# Shutdown_2019_v1_1.net
KiCad netlist of a schematic drawn in EAGLE
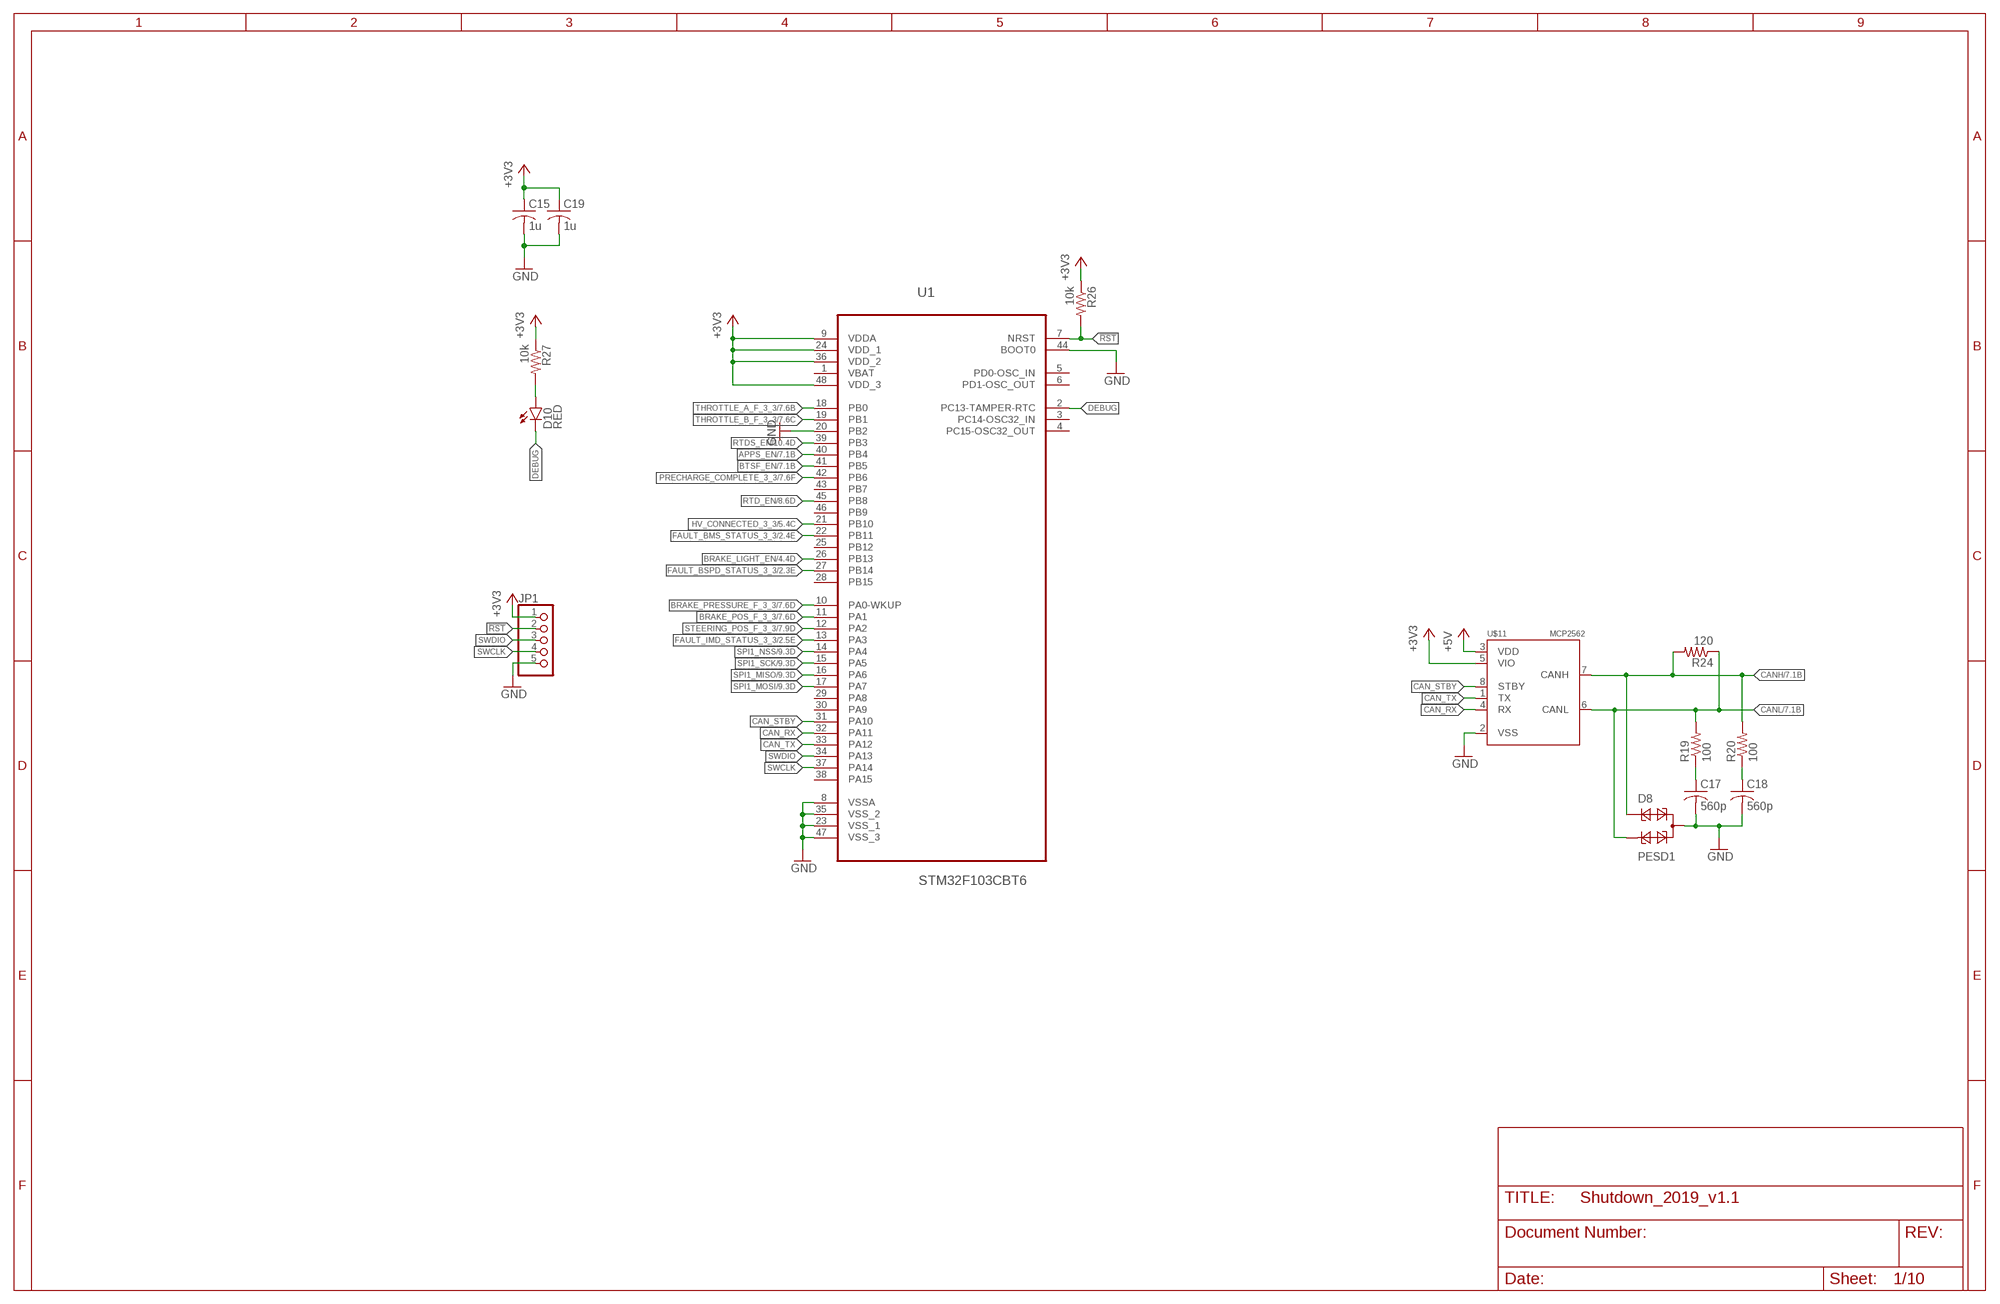
[diagram p0: schematic, sheet 1]
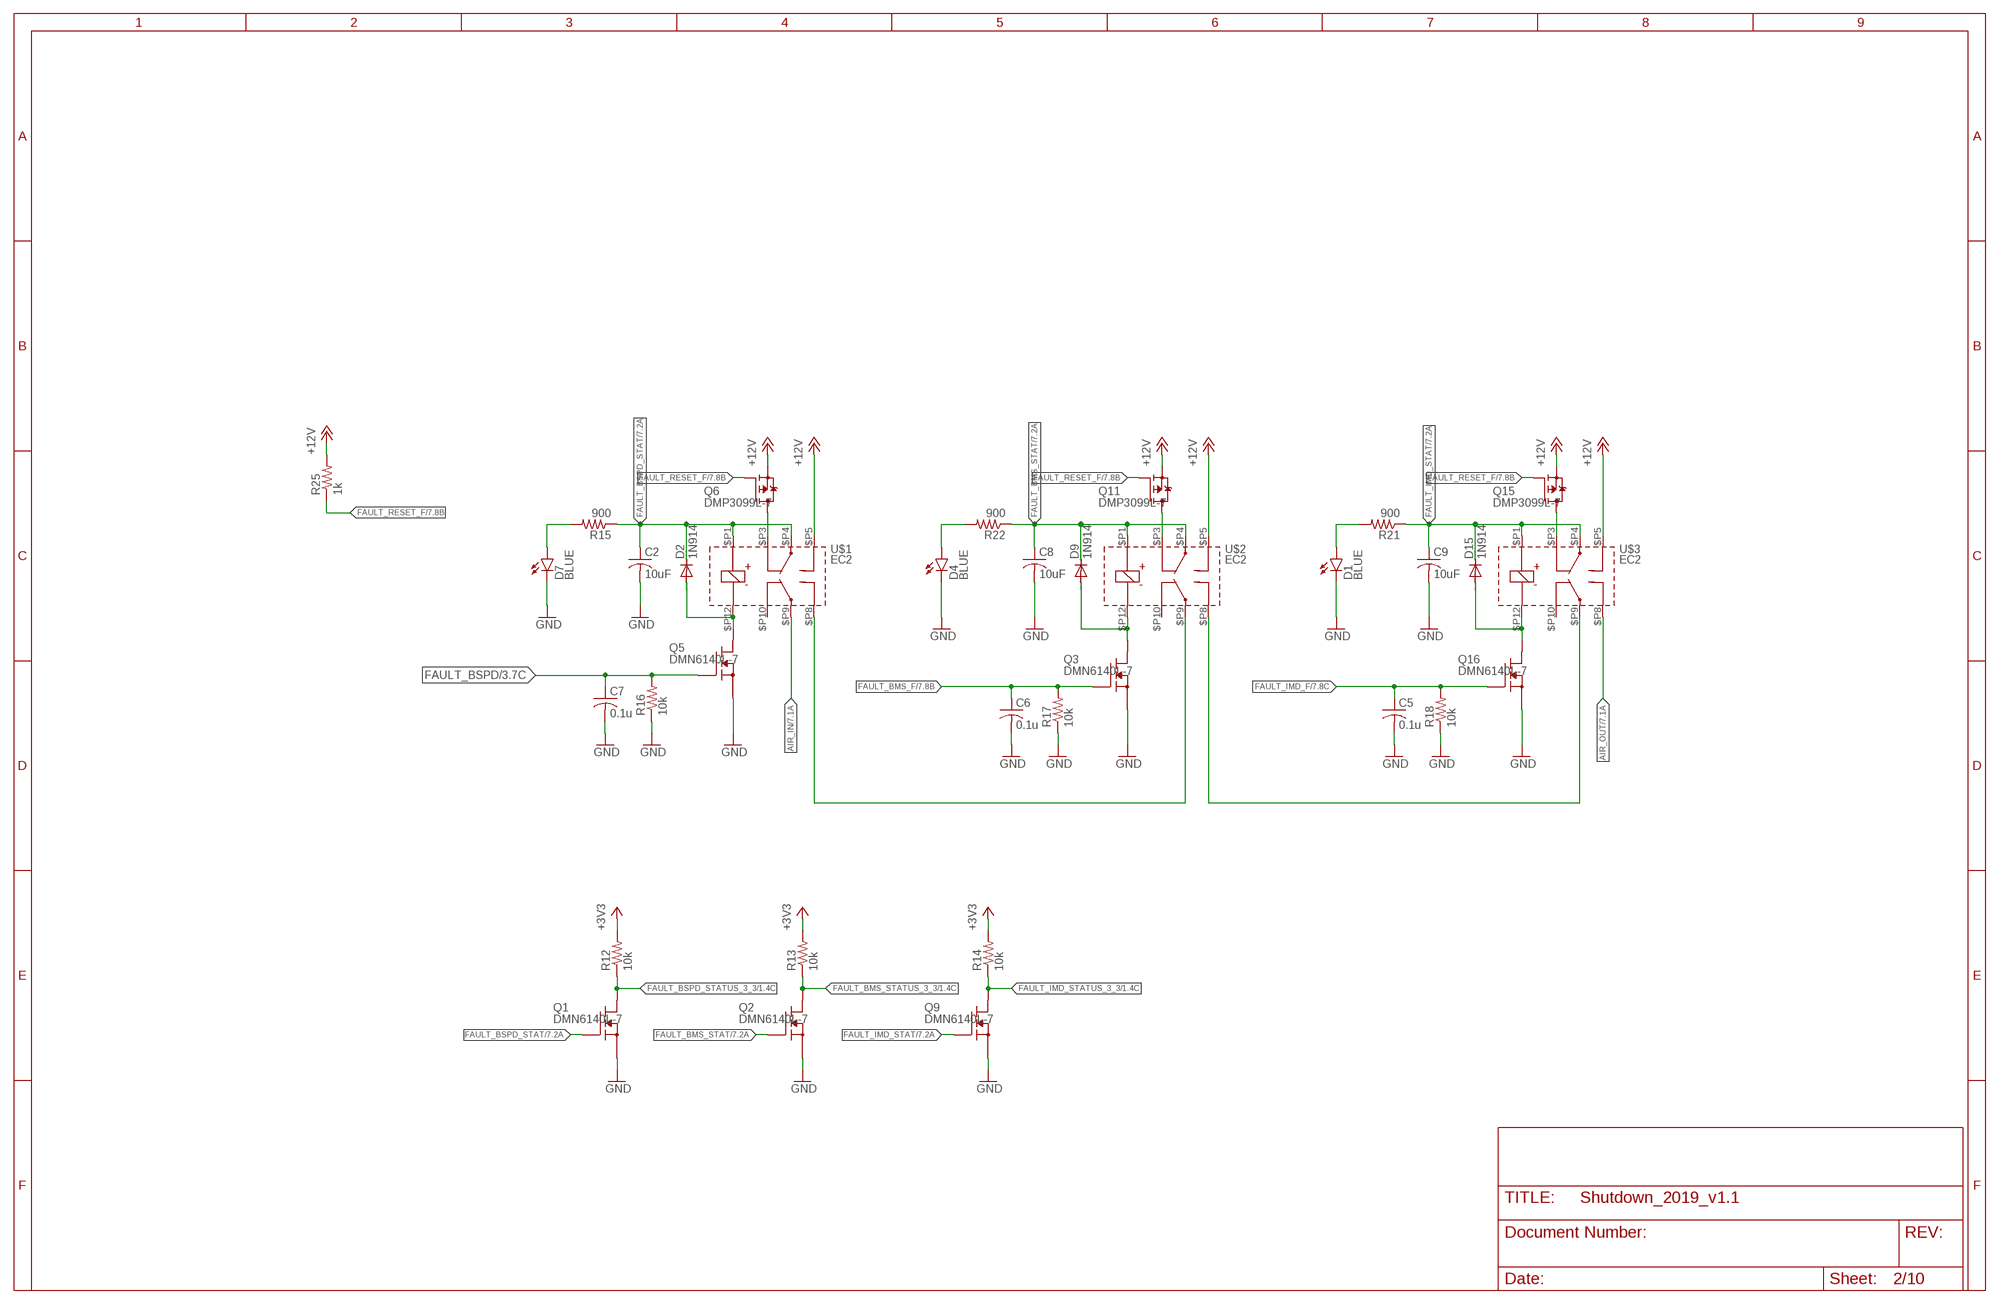
[diagram p1: schematic, sheet 2]
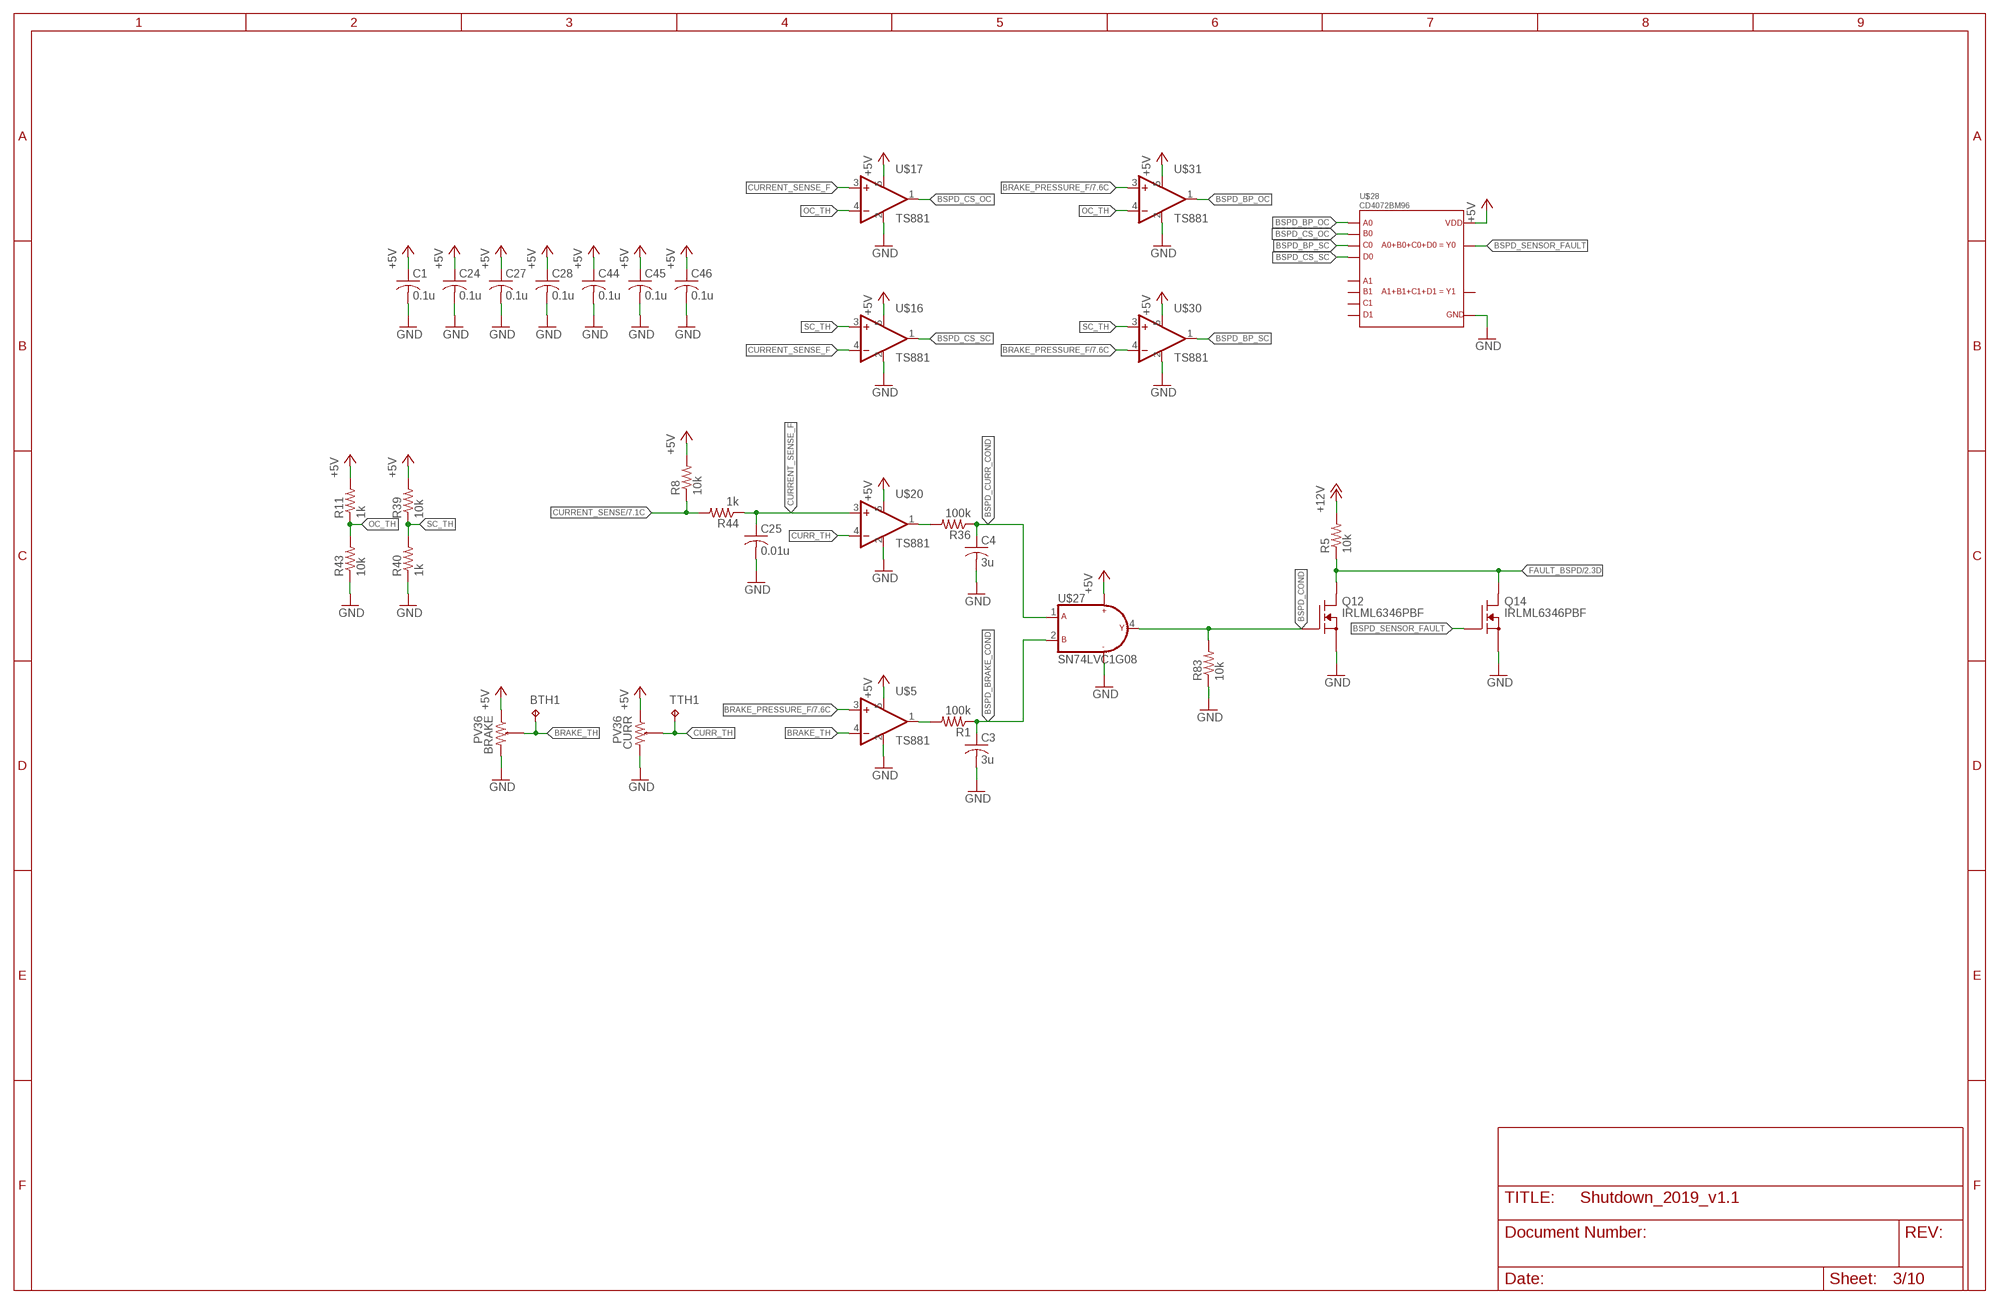
[diagram p2: schematic, sheet 3]
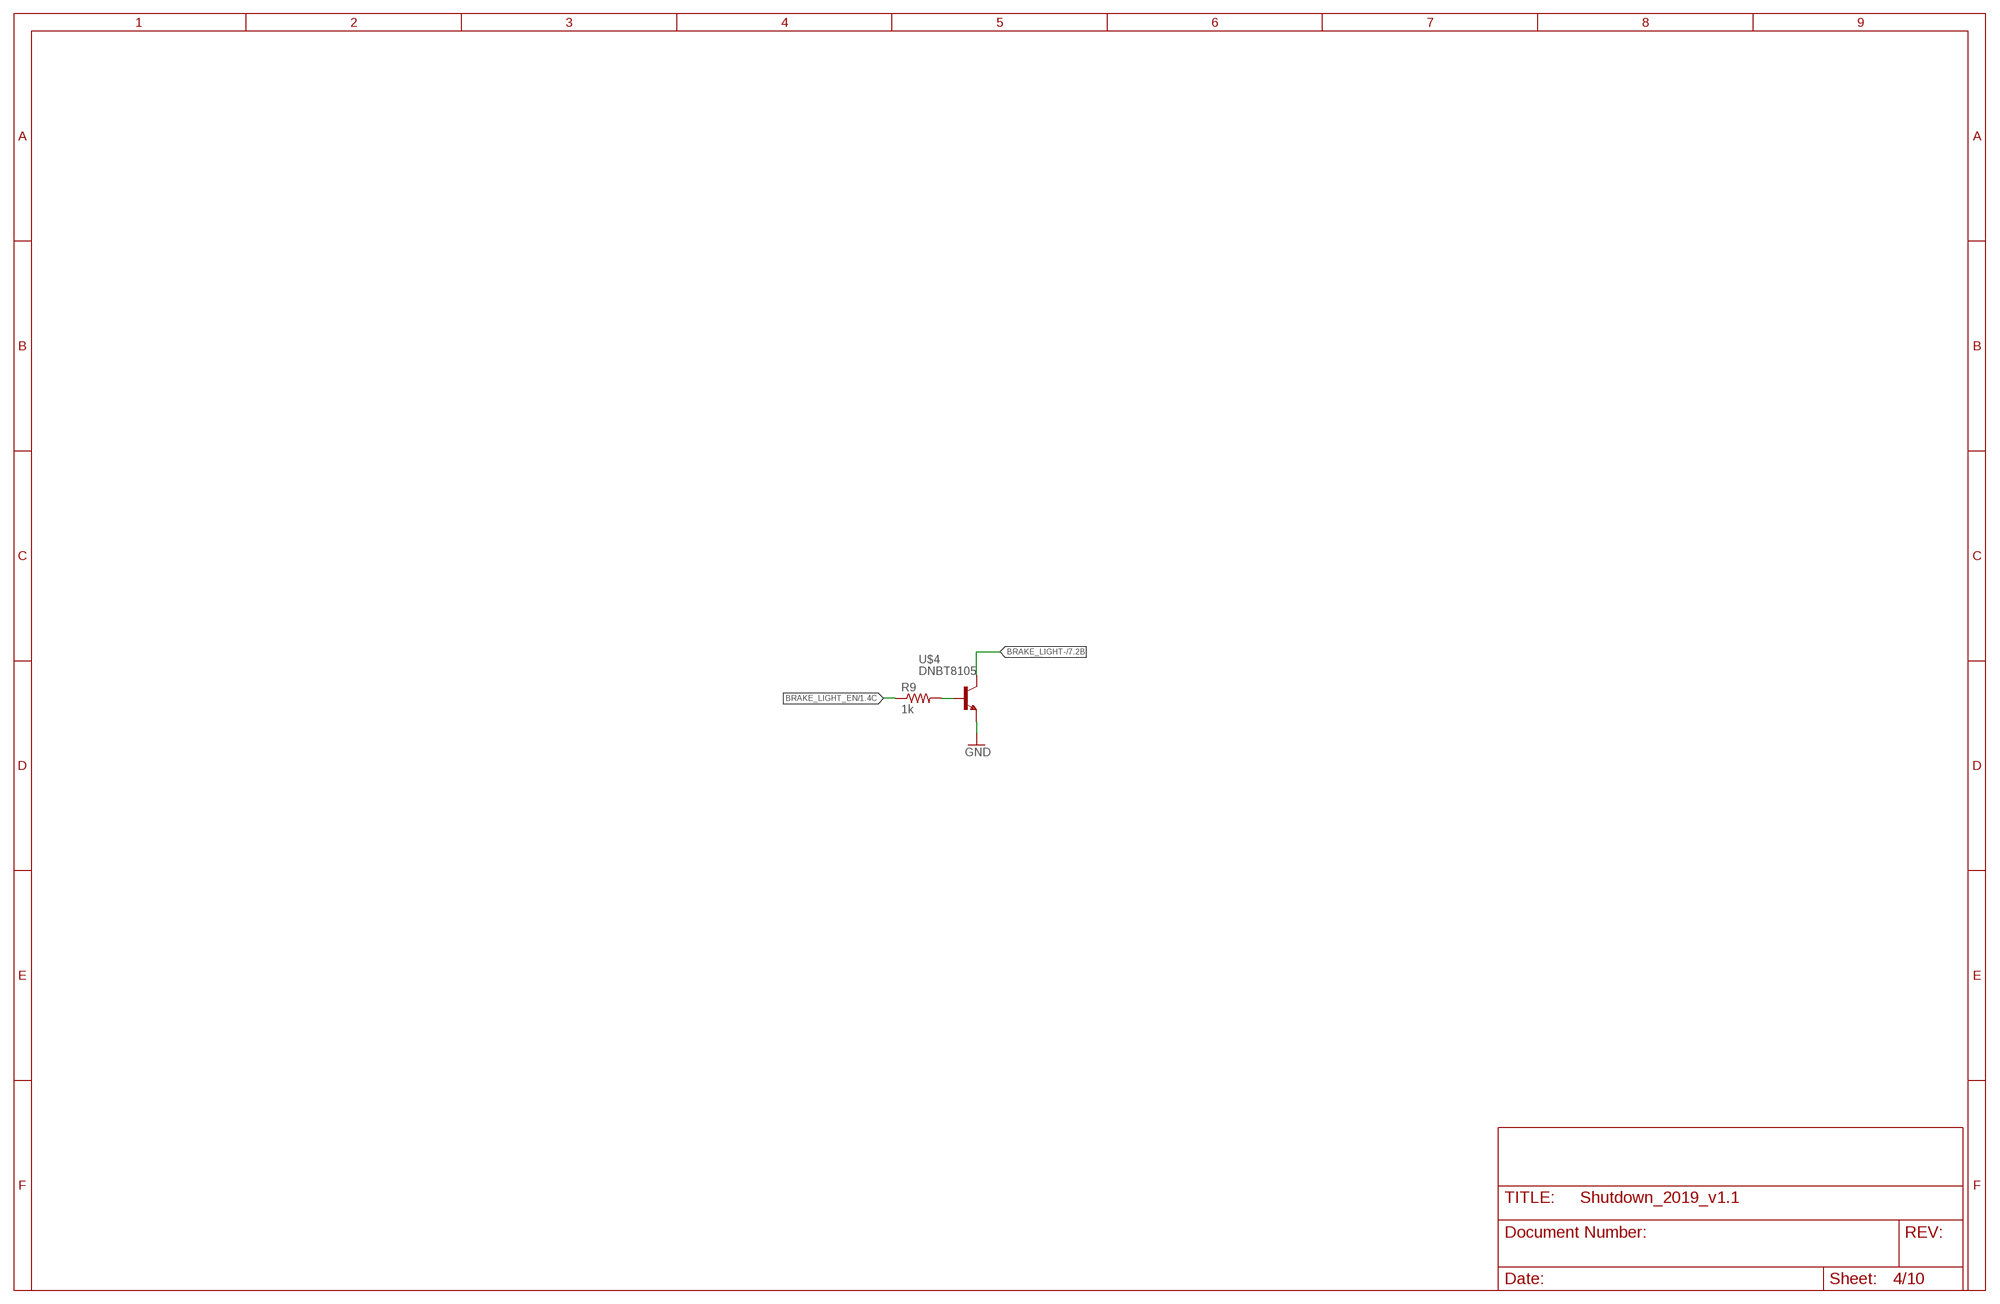
[diagram p3: schematic, sheet 4]
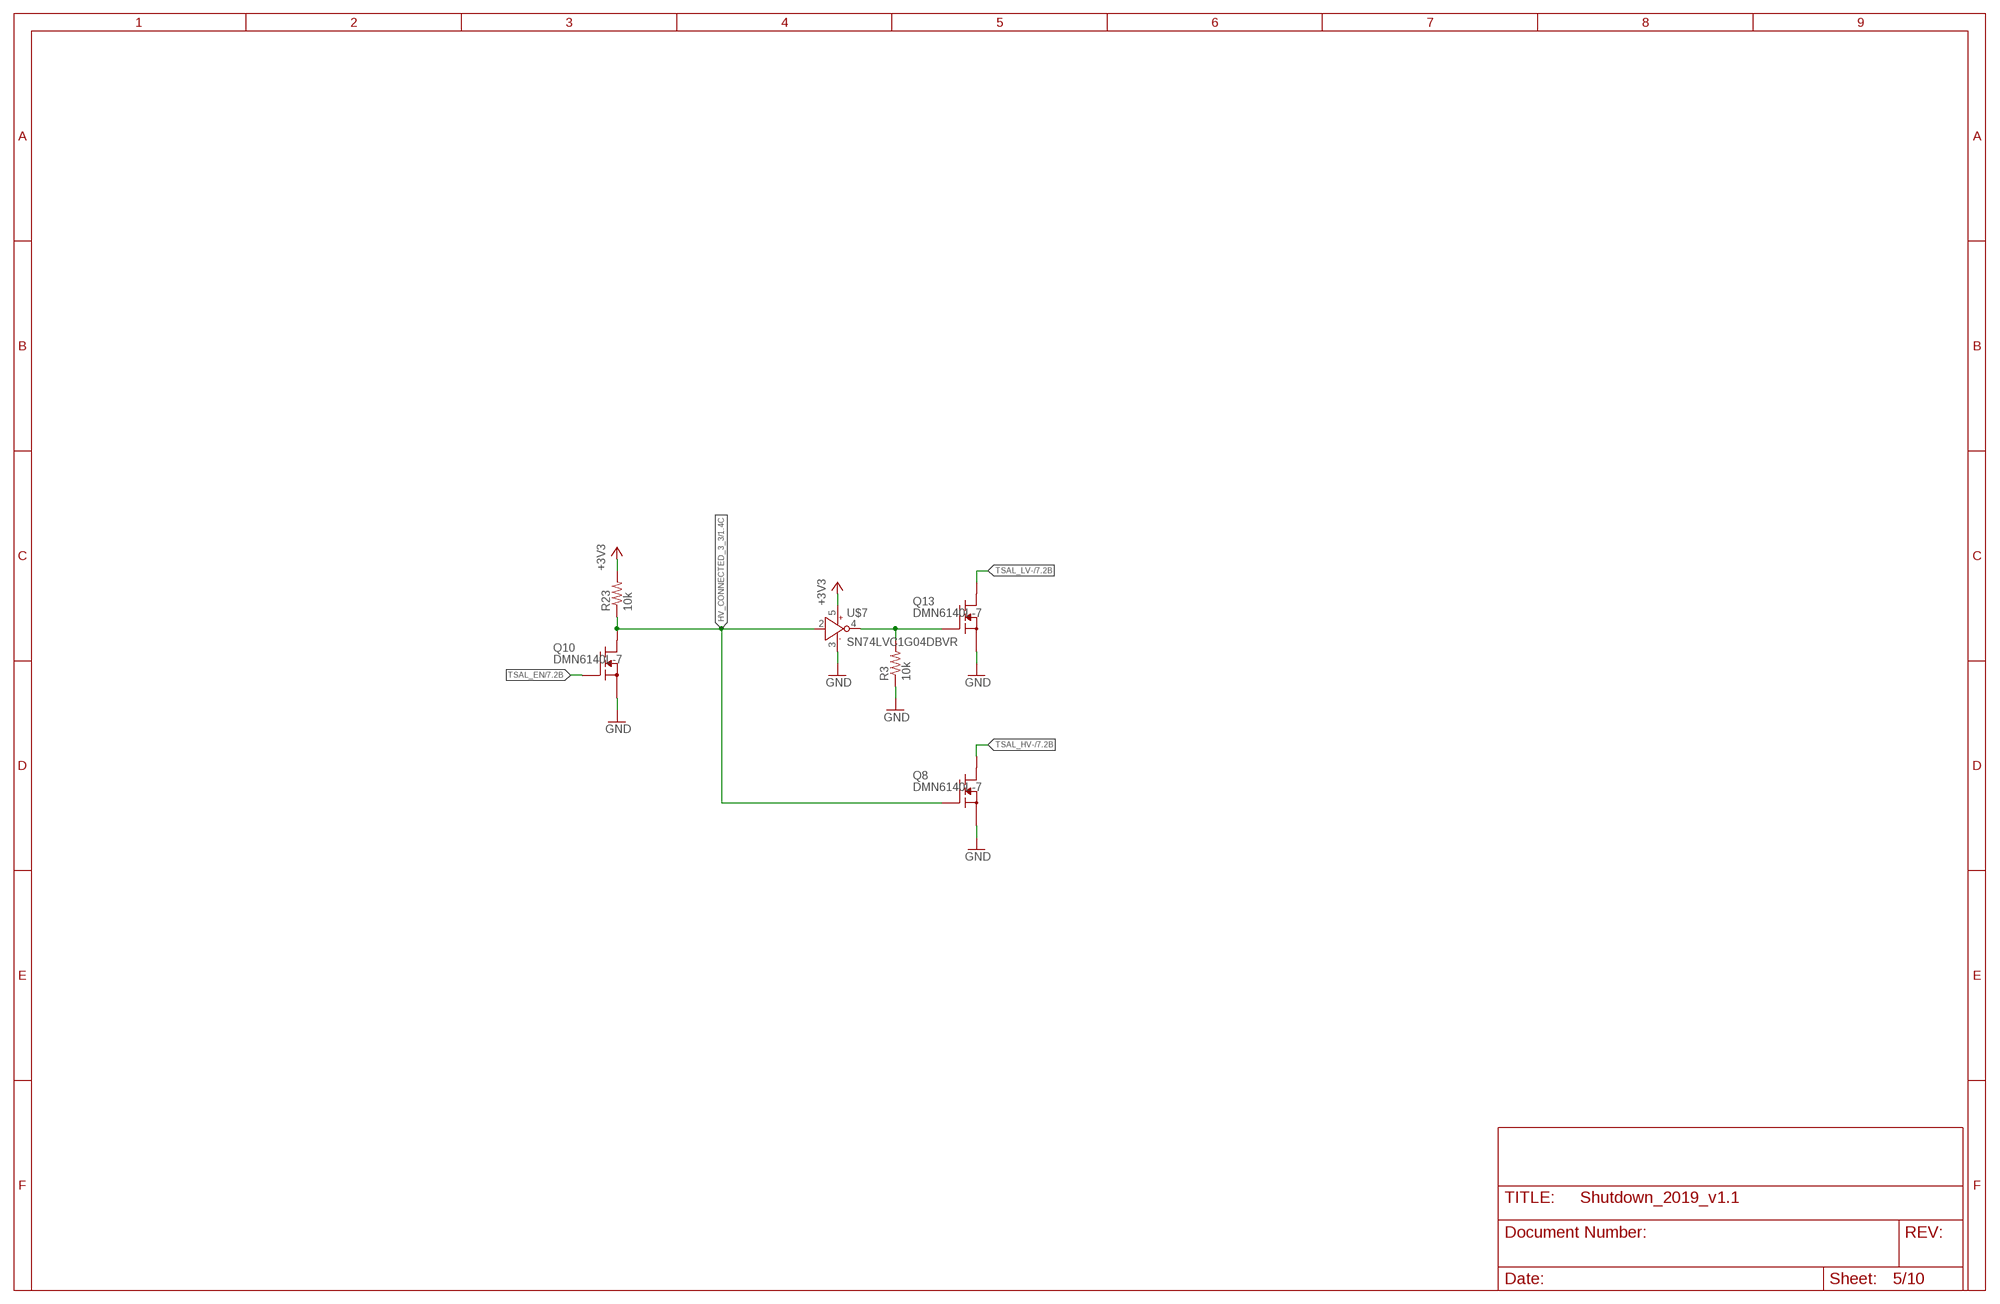
[diagram p4: schematic, sheet 5]
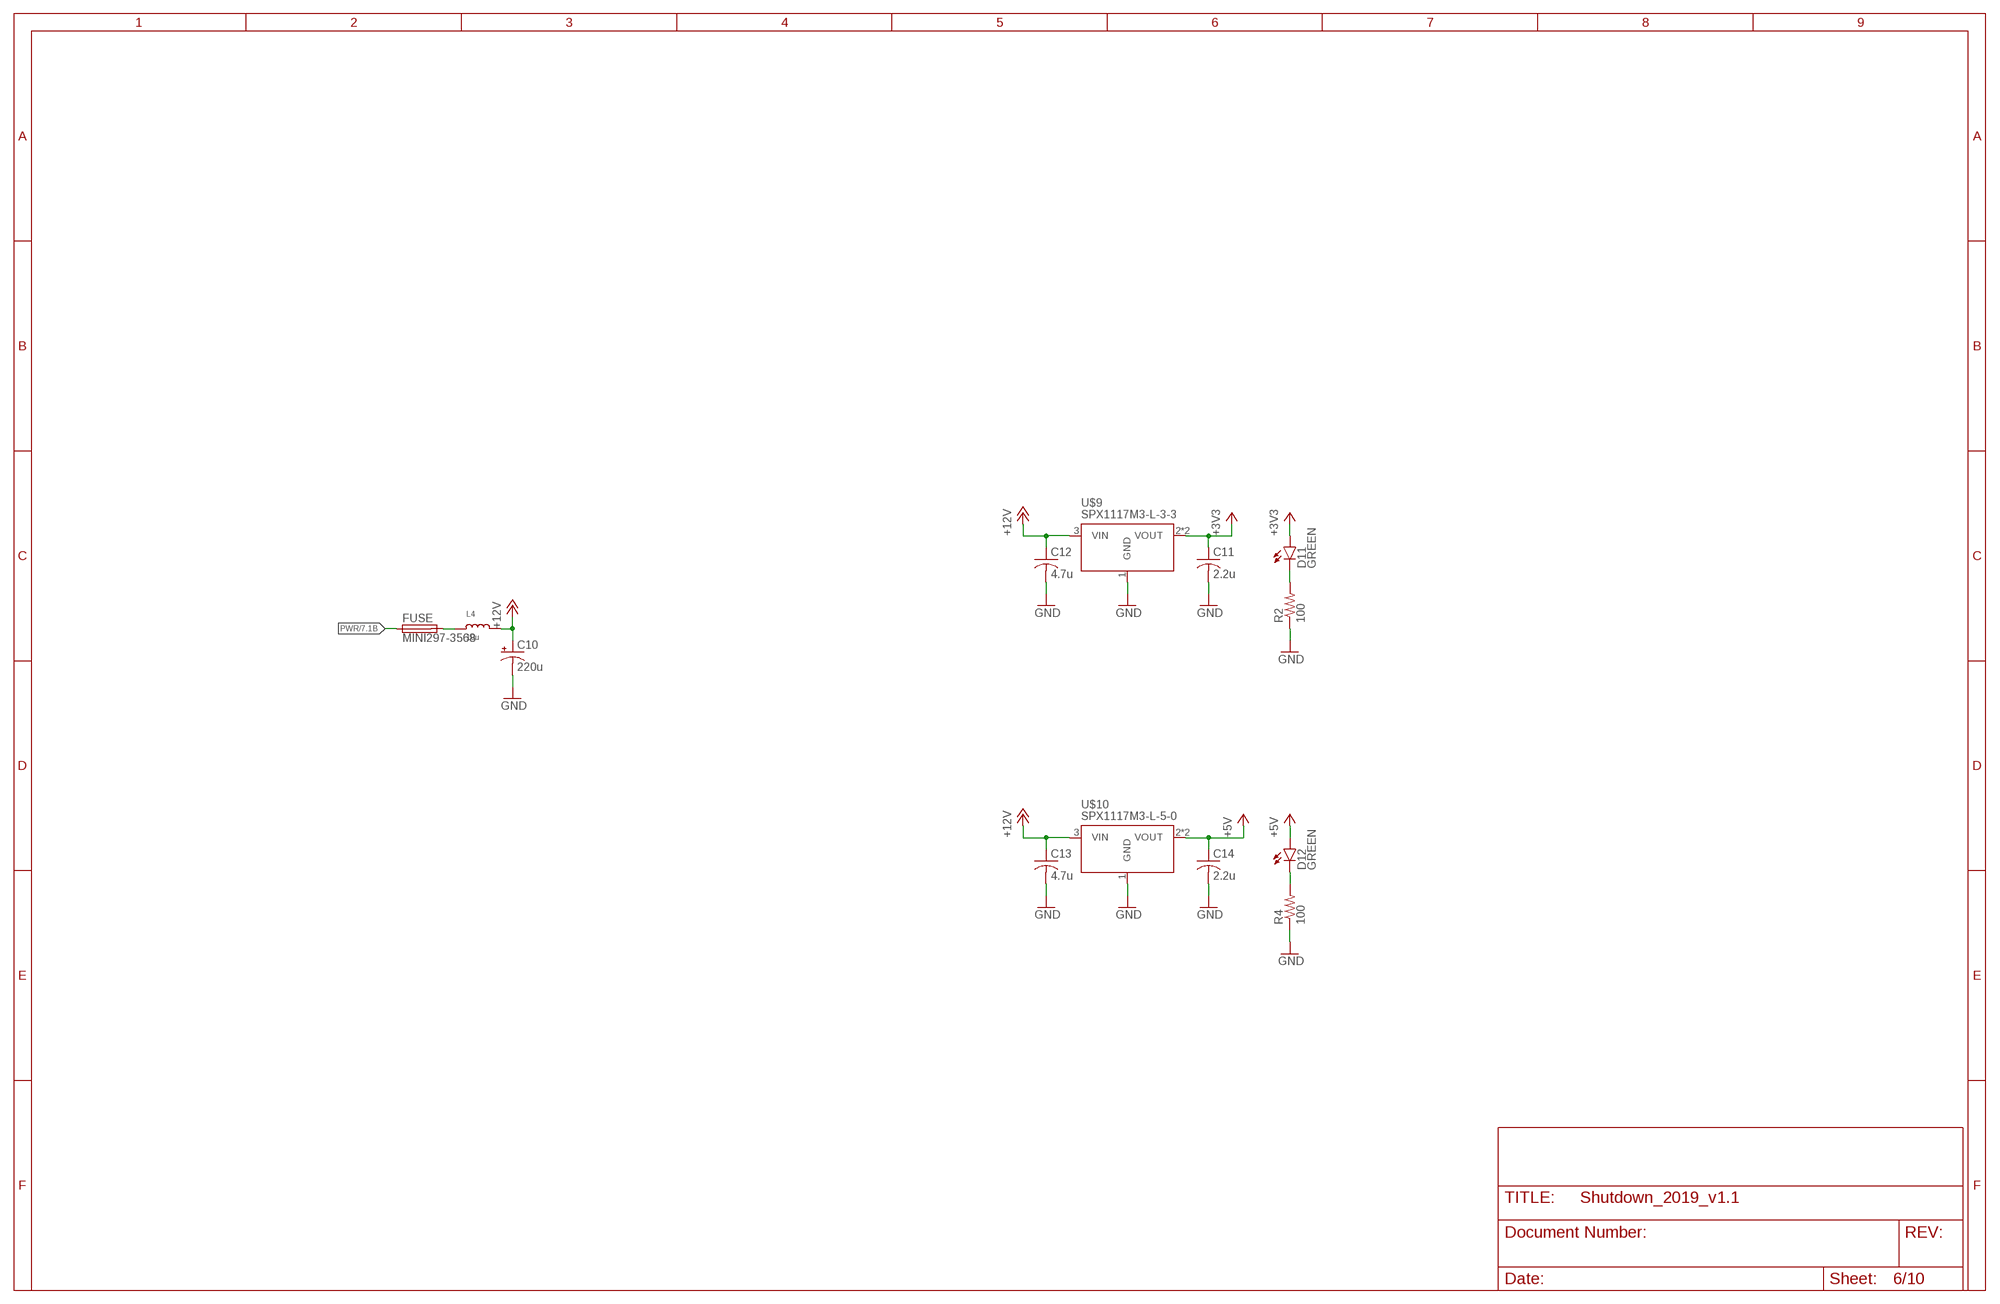
[diagram p5: schematic, sheet 6]
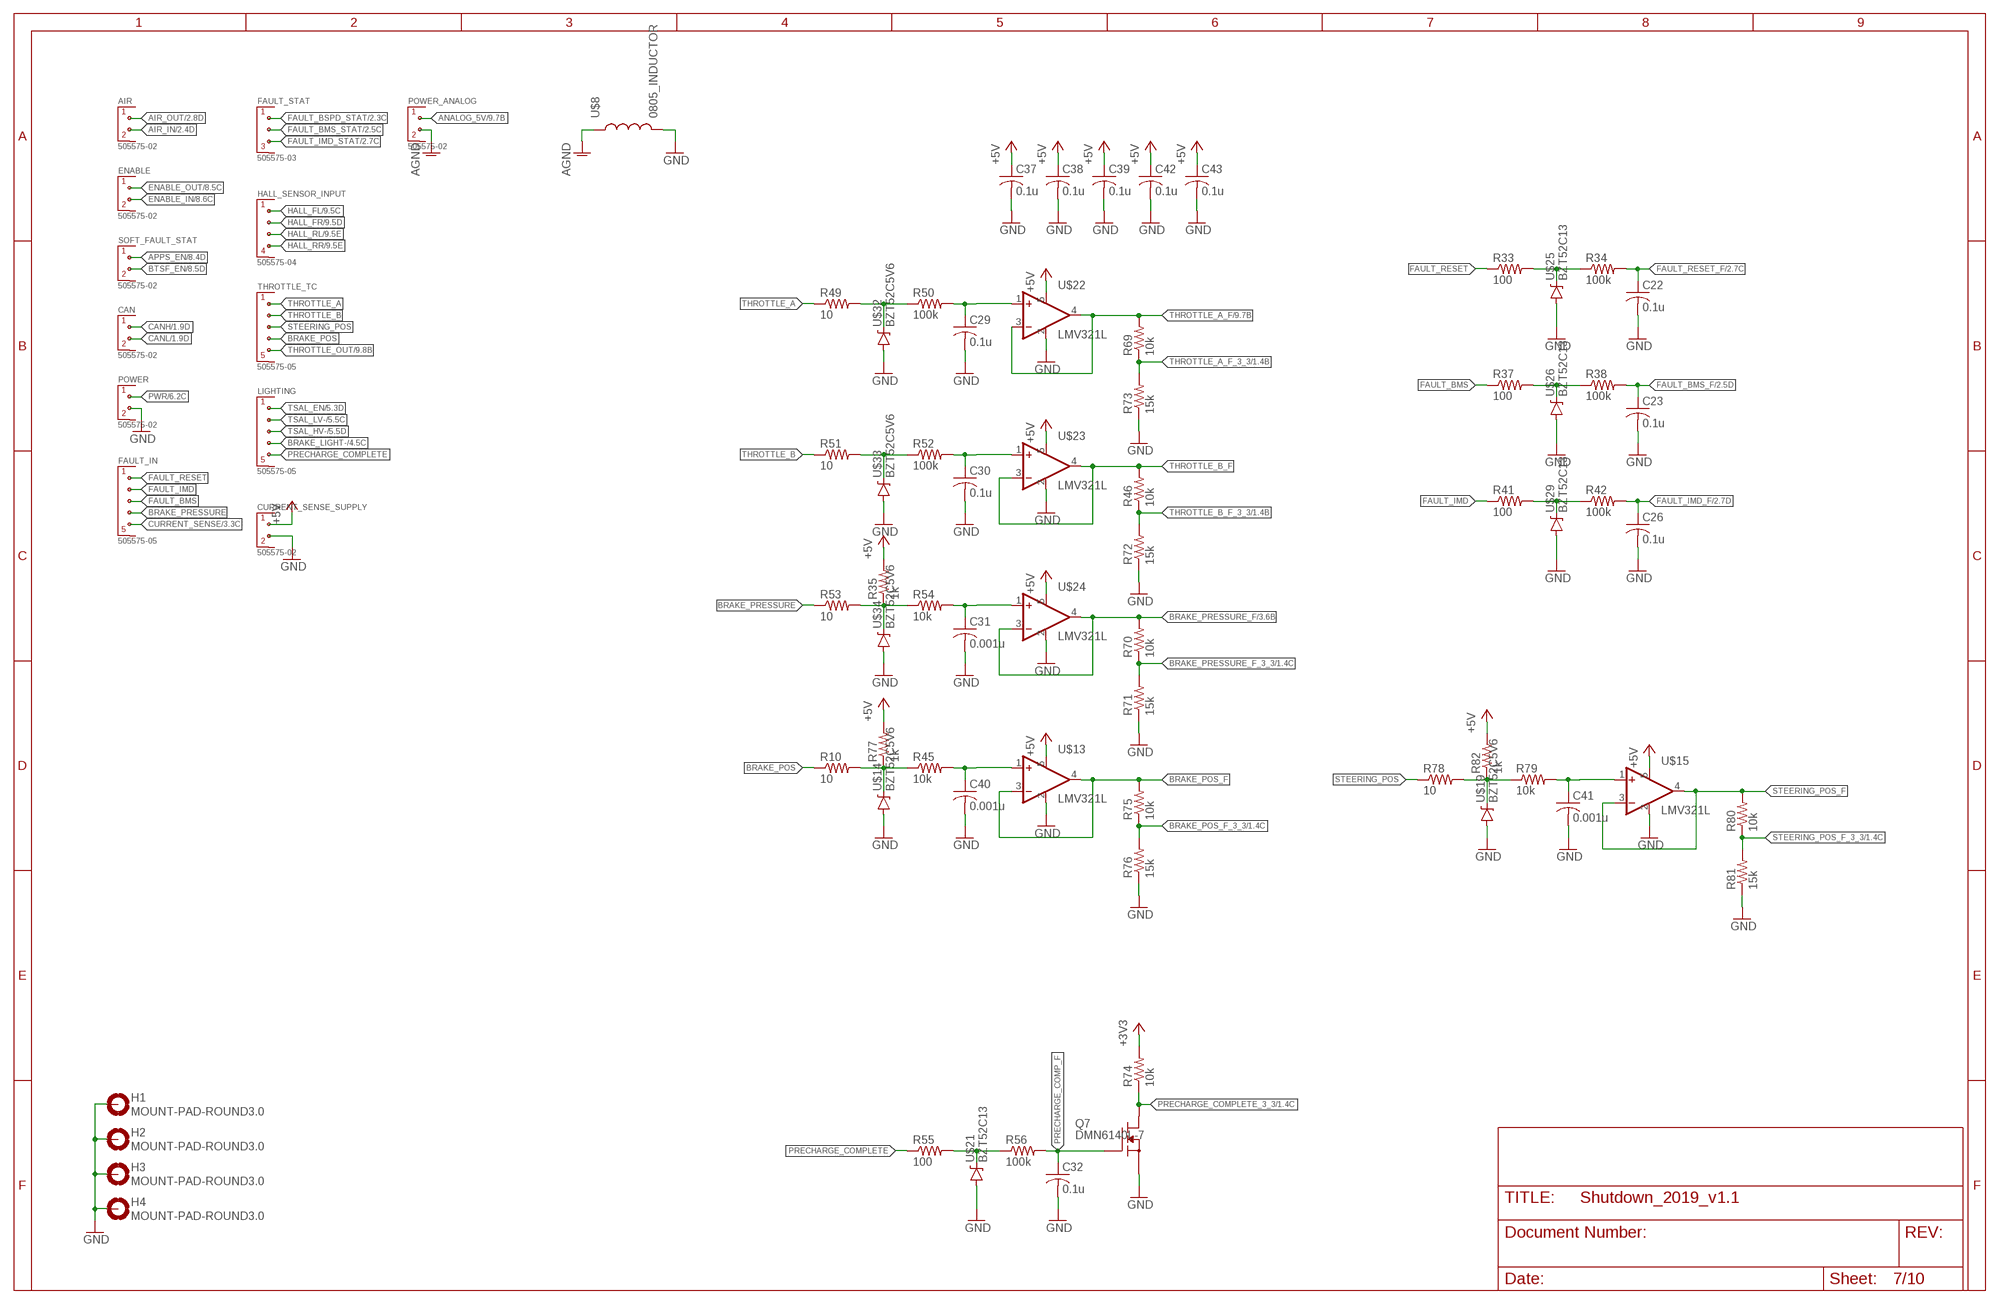
[diagram p6: schematic, sheet 7]
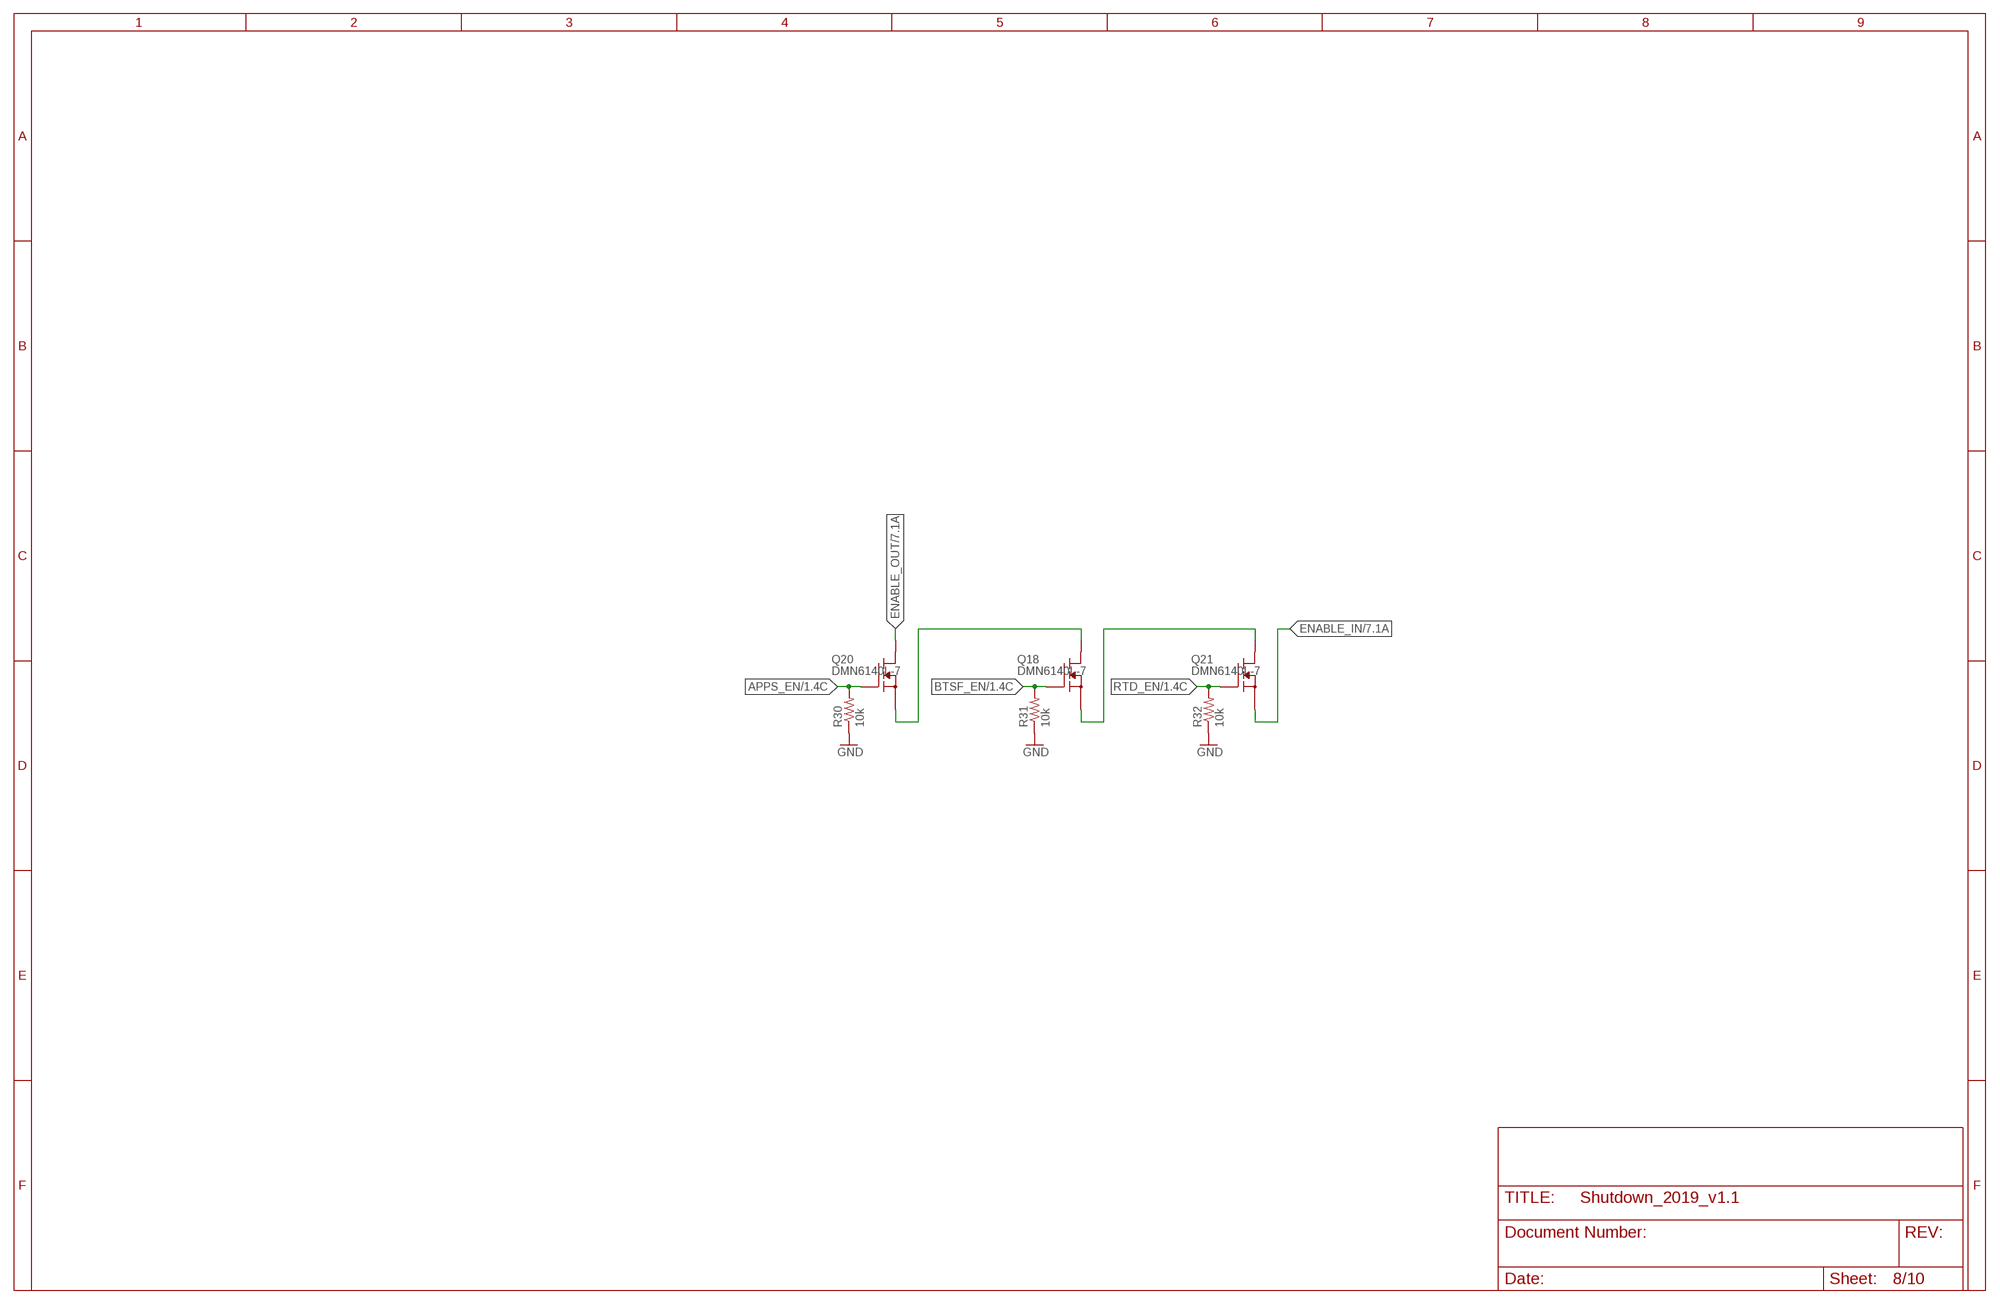
[diagram p7: schematic, sheet 8]
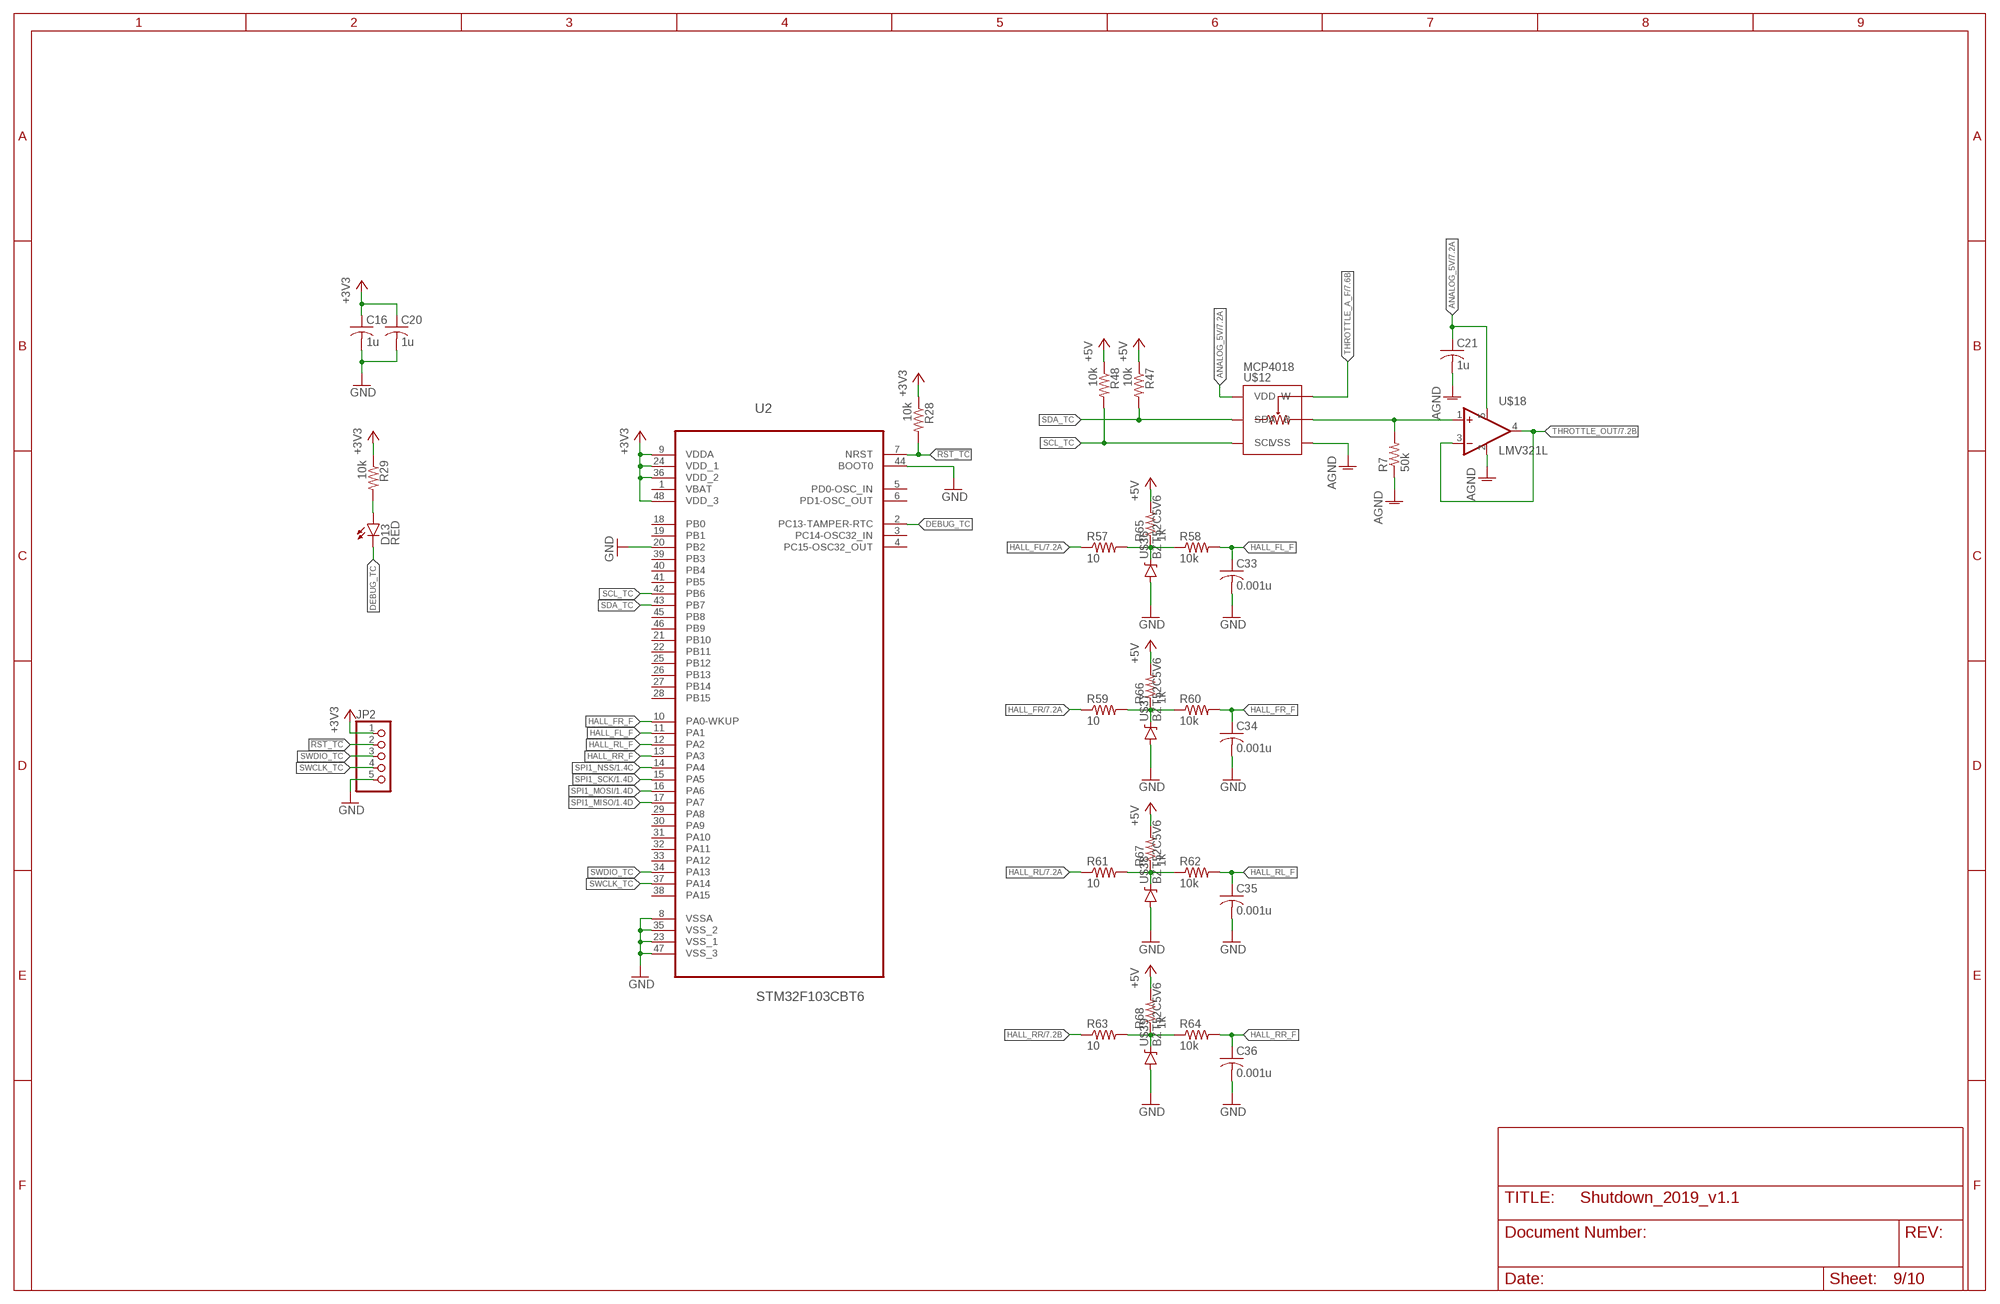
[diagram p8: schematic, sheet 9]
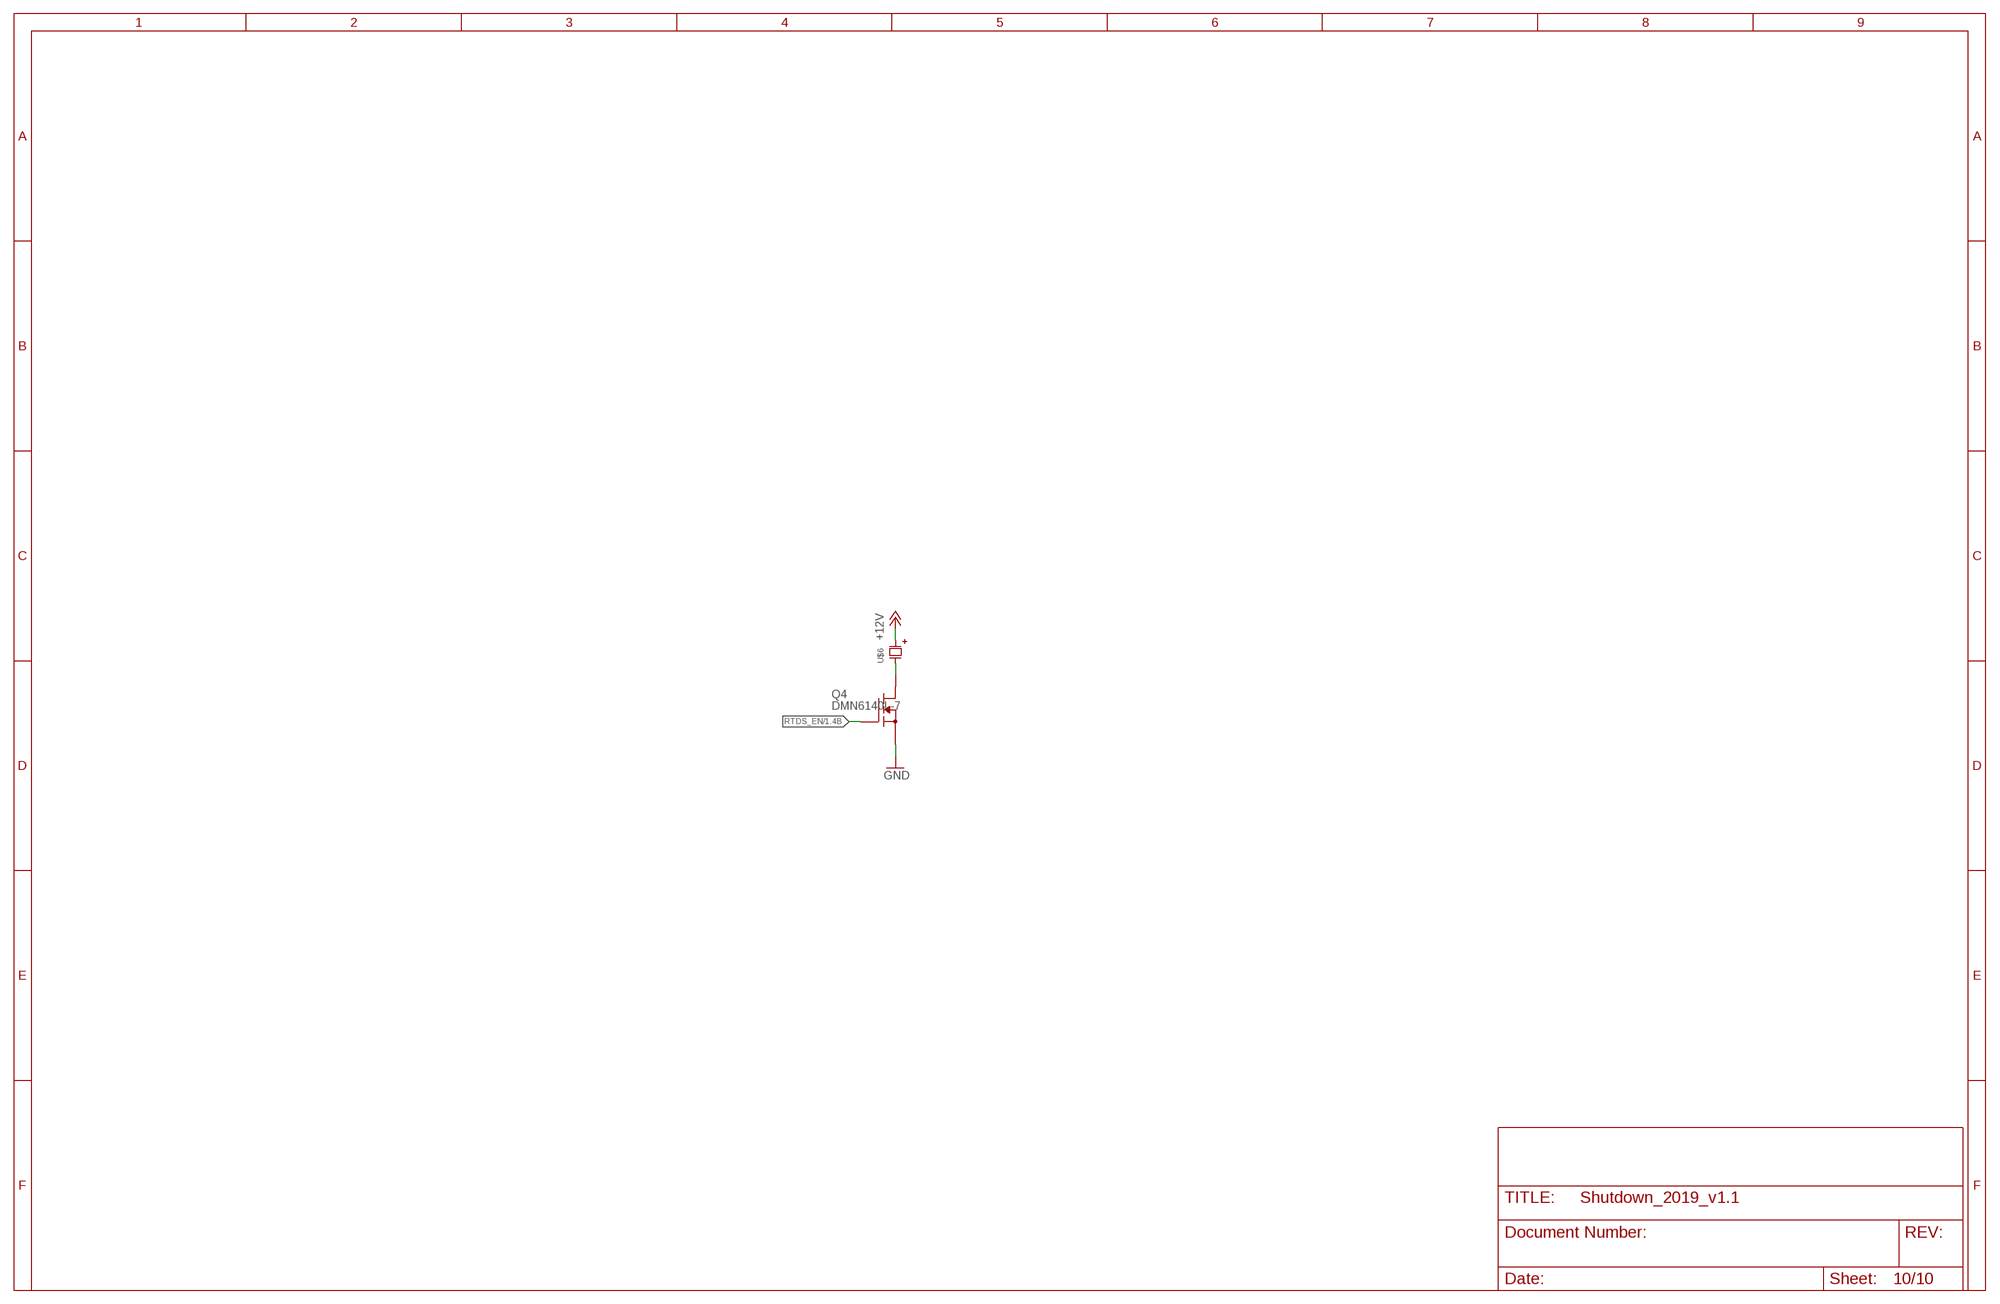
[diagram p9: schematic, sheet 10]

(export (version "E")
  (design (tool "Eeschema 10.0.6"))
  (components
    (comp (ref "Q4")
      (value "DMN6140L-7")
      (footprint "eagle-import:SOT23")
      (libsource (lib "eagle-import") (part "DMN6140L-7"))
    )
    (comp (ref "U$6")
      (value "MAS806Q")
      (footprint "eagle-import:MAS806Q")
      (libsource (lib "eagle-import") (part "MAS806Q"))
    )
    (comp (ref "BRAKE")
      (value "PV36")
      (footprint "eagle-import:PV36")
      (libsource (lib "eagle-import") (part "PV36"))
    )
    (comp (ref "BTH1")
      (value "TPTP09R")
      (footprint "eagle-import:TP09R")
      (libsource (lib "eagle-import") (part "TPTP09R"))
    )
    (comp (ref "C1")
      (value "0.1u")
      (footprint "eagle-import:C0603")
      (libsource (lib "eagle-import") (part "resistor_348_C-USC0603"))
    )
    (comp (ref "C3")
      (value "3u")
      (footprint "eagle-import:C0603")
      (libsource (lib "eagle-import") (part "resistor_348_C-USC0603"))
    )
    (comp (ref "C4")
      (value "3u")
      (footprint "eagle-import:C0603")
      (libsource (lib "eagle-import") (part "resistor_348_C-USC0603"))
    )
    (comp (ref "C24")
      (value "0.1u")
      (footprint "eagle-import:C0603")
      (libsource (lib "eagle-import") (part "resistor_348_C-USC0603"))
    )
    (comp (ref "C25")
      (value "0.01u")
      (footprint "eagle-import:C0603")
      (libsource (lib "eagle-import") (part "resistor_348_C-USC0603"))
    )
    (comp (ref "C27")
      (value "0.1u")
      (footprint "eagle-import:C0603")
      (libsource (lib "eagle-import") (part "resistor_348_C-USC0603"))
    )
    (comp (ref "C28")
      (value "0.1u")
      (footprint "eagle-import:C0603")
      (libsource (lib "eagle-import") (part "resistor_348_C-USC0603"))
    )
    (comp (ref "C44")
      (value "0.1u")
      (footprint "eagle-import:C0603")
      (libsource (lib "eagle-import") (part "resistor_348_C-USC0603"))
    )
    (comp (ref "C45")
      (value "0.1u")
      (footprint "eagle-import:C0603")
      (libsource (lib "eagle-import") (part "resistor_348_C-USC0603"))
    )
    (comp (ref "C46")
      (value "0.1u")
      (footprint "eagle-import:C0603")
      (libsource (lib "eagle-import") (part "resistor_348_C-USC0603"))
    )
    (comp (ref "CURR")
      (value "PV36")
      (footprint "eagle-import:PV36")
      (libsource (lib "eagle-import") (part "PV36"))
    )
    (comp (ref "Q12")
      (value "IRLML6346PBF")
      (footprint "eagle-import:SOT23")
      (libsource (lib "eagle-import") (part "IRLML6346PBF"))
    )
    (comp (ref "Q14")
      (value "IRLML6346PBF")
      (footprint "eagle-import:SOT23")
      (libsource (lib "eagle-import") (part "IRLML6346PBF"))
    )
    (comp (ref "R1")
      (value "100k")
      (footprint "eagle-import:R0603")
      (libsource (lib "eagle-import") (part "resistor_348_R-US_R0603"))
    )
    (comp (ref "R5")
      (value "10k")
      (footprint "eagle-import:R0603")
      (libsource (lib "eagle-import") (part "resistor_348_R-US_R0603"))
    )
    (comp (ref "R8")
      (value "10k")
      (footprint "eagle-import:R0603")
      (libsource (lib "eagle-import") (part "resistor_348_R-US_R0603"))
    )
    (comp (ref "R11")
      (value "1k")
      (footprint "eagle-import:R0603")
      (libsource (lib "eagle-import") (part "resistor_348_R-US_R0603"))
    )
    (comp (ref "R36")
      (value "100k")
      (footprint "eagle-import:R0603")
      (libsource (lib "eagle-import") (part "resistor_348_R-US_R0603"))
    )
    (comp (ref "R39")
      (value "10k")
      (footprint "eagle-import:R0603")
      (libsource (lib "eagle-import") (part "resistor_348_R-US_R0603"))
    )
    (comp (ref "R40")
      (value "1k")
      (footprint "eagle-import:R0603")
      (libsource (lib "eagle-import") (part "resistor_348_R-US_R0603"))
    )
    (comp (ref "R43")
      (value "10k")
      (footprint "eagle-import:R0603")
      (libsource (lib "eagle-import") (part "resistor_348_R-US_R0603"))
    )
    (comp (ref "R44")
      (value "1k")
      (footprint "eagle-import:R0603")
      (libsource (lib "eagle-import") (part "resistor_348_R-US_R0603"))
    )
    (comp (ref "R83")
      (value "10k")
      (footprint "eagle-import:R0603")
      (libsource (lib "eagle-import") (part "resistor_348_R-US_R0603"))
    )
    (comp (ref "TTH1")
      (value "TPTP09R")
      (footprint "eagle-import:TP09R")
      (libsource (lib "eagle-import") (part "TPTP09R"))
    )
    (comp (ref "U$5")
      (value "TS881")
      (footprint "eagle-import:SOT23-5")
      (libsource (lib "eagle-import") (part "TS881"))
    )
    (comp (ref "U$16")
      (value "TS881")
      (footprint "eagle-import:SOT23-5")
      (libsource (lib "eagle-import") (part "TS881"))
    )
    (comp (ref "U$17")
      (value "TS881")
      (footprint "eagle-import:SOT23-5")
      (libsource (lib "eagle-import") (part "TS881"))
    )
    (comp (ref "U$20")
      (value "TS881")
      (footprint "eagle-import:SOT23-5")
      (libsource (lib "eagle-import") (part "TS881"))
    )
    (comp (ref "U$27")
      (value "SN74LVC1G08")
      (footprint "eagle-import:SOT23-5")
      (libsource (lib "eagle-import") (part "SN74LVC1G08"))
    )
    (comp (ref "U$28")
      (value "CD4072BM96")
      (footprint "eagle-import:SOIC8")
      (libsource (lib "eagle-import") (part "CD4072B"))
    )
    (comp (ref "U$30")
      (value "TS881")
      (footprint "eagle-import:SOT23-5")
      (libsource (lib "eagle-import") (part "TS881"))
    )
    (comp (ref "U$31")
      (value "TS881")
      (footprint "eagle-import:SOT23-5")
      (libsource (lib "eagle-import") (part "TS881"))
    )
    (comp (ref "C15")
      (value "1u")
      (footprint "eagle-import:C0805")
      (libsource (lib "eagle-import") (part "C-USC0805"))
    )
    (comp (ref "C17")
      (value "560p")
      (footprint "eagle-import:C0603")
      (libsource (lib "eagle-import") (part "C-USC0603"))
    )
    (comp (ref "C18")
      (value "560p")
      (footprint "eagle-import:C0603")
      (libsource (lib "eagle-import") (part "C-USC0603"))
    )
    (comp (ref "C19")
      (value "1u")
      (footprint "eagle-import:C0805")
      (libsource (lib "eagle-import") (part "C-USC0805"))
    )
    (comp (ref "D8")
      (value "PESD1")
      (footprint "eagle-import:SOT23")
      (libsource (lib "eagle-import") (part "PESD1CAN"))
    )
    (comp (ref "D10")
      (value "RED")
      (footprint "eagle-import:LED-0603")
      (libsource (lib "eagle-import") (part "LED-RED0603"))
    )
    (comp (ref "JP1")
      (value "PINHD-1X5")
      (footprint "eagle-import:1X05")
      (libsource (lib "eagle-import") (part "PINHD-1X5"))
    )
    (comp (ref "R19")
      (value "100")
      (footprint "eagle-import:R0603")
      (libsource (lib "eagle-import") (part "R-US_R0603"))
    )
    (comp (ref "R20")
      (value "100")
      (footprint "eagle-import:R0603")
      (libsource (lib "eagle-import") (part "R-US_R0603"))
    )
    (comp (ref "R24")
      (value "120")
      (footprint "eagle-import:R0603")
      (libsource (lib "eagle-import") (part "R-US_R0603"))
    )
    (comp (ref "R26")
      (value "10k")
      (footprint "eagle-import:R0603")
      (libsource (lib "eagle-import") (part "R-US_R0603"))
    )
    (comp (ref "R27")
      (value "10k")
      (footprint "eagle-import:R0603")
      (libsource (lib "eagle-import") (part "R-US_R0603"))
    )
    (comp (ref "U$11")
      (value "MCP2562")
      (footprint "eagle-import:SOIC8")
      (libsource (lib "eagle-import") (part "MCP2562"))
    )
    (comp (ref "U1")
      (value "STM32F103CBT6")
      (footprint "eagle-import:QFP50P900X900X160-48N")
      (libsource (lib "eagle-import") (part "STM32F103CBT6"))
    )
    (comp (ref "C2")
      (value "10uF")
      (footprint "eagle-import:C0805")
      (libsource (lib "eagle-import") (part "C-USC0805"))
    )
    (comp (ref "C5")
      (value "0.1u")
      (footprint "eagle-import:C0603")
      (libsource (lib "eagle-import") (part "resistor_348_C-USC0603"))
    )
    (comp (ref "C6")
      (value "0.1u")
      (footprint "eagle-import:C0603")
      (libsource (lib "eagle-import") (part "resistor_348_C-USC0603"))
    )
    (comp (ref "C7")
      (value "0.1u")
      (footprint "eagle-import:C0603")
      (libsource (lib "eagle-import") (part "resistor_348_C-USC0603"))
    )
    (comp (ref "C8")
      (value "10uF")
      (footprint "eagle-import:C0805")
      (libsource (lib "eagle-import") (part "C-USC0805"))
    )
    (comp (ref "C9")
      (value "10uF")
      (footprint "eagle-import:C0805")
      (libsource (lib "eagle-import") (part "C-USC0805"))
    )
    (comp (ref "D1")
      (value "BLUE")
      (footprint "eagle-import:LED-0603")
      (libsource (lib "eagle-import") (part "LED-BLUE0603"))
    )
    (comp (ref "D2")
      (value "1N914")
      (footprint "eagle-import:SOD323-F")
      (libsource (lib "eagle-import") (part "1N914"))
    )
    (comp (ref "D4")
      (value "BLUE")
      (footprint "eagle-import:LED-0603")
      (libsource (lib "eagle-import") (part "LED-BLUE0603"))
    )
    (comp (ref "D7")
      (value "BLUE")
      (footprint "eagle-import:LED-0603")
      (libsource (lib "eagle-import") (part "LED-BLUE0603"))
    )
    (comp (ref "D9")
      (value "1N914")
      (footprint "eagle-import:SOD323-F")
      (libsource (lib "eagle-import") (part "1N914"))
    )
    (comp (ref "D15")
      (value "1N914")
      (footprint "eagle-import:SOD323-F")
      (libsource (lib "eagle-import") (part "1N914"))
    )
    (comp (ref "Q1")
      (value "DMN6140L-7")
      (footprint "eagle-import:SOT23")
      (libsource (lib "eagle-import") (part "DMN6140L-7"))
    )
    (comp (ref "Q2")
      (value "DMN6140L-7")
      (footprint "eagle-import:SOT23")
      (libsource (lib "eagle-import") (part "DMN6140L-7"))
    )
    (comp (ref "Q3")
      (value "DMN6140L-7")
      (footprint "eagle-import:SOT23")
      (libsource (lib "eagle-import") (part "DMN6140L-7"))
    )
    (comp (ref "Q5")
      (value "DMN6140L-7")
      (footprint "eagle-import:SOT23")
      (libsource (lib "eagle-import") (part "DMN6140L-7"))
    )
    (comp (ref "Q6")
      (value "DMP3099L-7")
      (footprint "eagle-import:SOT23")
      (libsource (lib "eagle-import") (part "DMP3099L-7"))
    )
    (comp (ref "Q9")
      (value "DMN6140L-7")
      (footprint "eagle-import:SOT23")
      (libsource (lib "eagle-import") (part "DMN6140L-7"))
    )
    (comp (ref "Q11")
      (value "DMP3099L-7")
      (footprint "eagle-import:SOT23")
      (libsource (lib "eagle-import") (part "DMP3099L-7"))
    )
    (comp (ref "Q15")
      (value "DMP3099L-7")
      (footprint "eagle-import:SOT23")
      (libsource (lib "eagle-import") (part "DMP3099L-7"))
    )
    (comp (ref "Q16")
      (value "DMN6140L-7")
      (footprint "eagle-import:SOT23")
      (libsource (lib "eagle-import") (part "DMN6140L-7"))
    )
    (comp (ref "R12")
      (value "10k")
      (footprint "eagle-import:R0603")
      (libsource (lib "eagle-import") (part "resistor_348_R-US_R0603"))
    )
    (comp (ref "R13")
      (value "10k")
      (footprint "eagle-import:R0603")
      (libsource (lib "eagle-import") (part "resistor_348_R-US_R0603"))
    )
    (comp (ref "R14")
      (value "10k")
      (footprint "eagle-import:R0603")
      (libsource (lib "eagle-import") (part "resistor_348_R-US_R0603"))
    )
    (comp (ref "R15")
      (value "900")
      (footprint "eagle-import:R0603")
      (libsource (lib "eagle-import") (part "resistor_348_R-US_R0603"))
    )
    (comp (ref "R16")
      (value "10k")
      (footprint "eagle-import:R0603")
      (libsource (lib "eagle-import") (part "resistor_348_R-US_R0603"))
    )
    (comp (ref "R17")
      (value "10k")
      (footprint "eagle-import:R0603")
      (libsource (lib "eagle-import") (part "resistor_348_R-US_R0603"))
    )
    (comp (ref "R18")
      (value "10k")
      (footprint "eagle-import:R0603")
      (libsource (lib "eagle-import") (part "resistor_348_R-US_R0603"))
    )
    (comp (ref "R21")
      (value "900")
      (footprint "eagle-import:R0603")
      (libsource (lib "eagle-import") (part "resistor_348_R-US_R0603"))
    )
    (comp (ref "R22")
      (value "900")
      (footprint "eagle-import:R0603")
      (libsource (lib "eagle-import") (part "resistor_348_R-US_R0603"))
    )
    (comp (ref "R25")
      (value "1k")
      (footprint "eagle-import:R0603")
      (libsource (lib "eagle-import") (part "resistor_348_R-US_R0603"))
    )
    (comp (ref "U$1")
      (value "EC2")
      (footprint "eagle-import:DPDT_2.54")
      (libsource (lib "eagle-import") (part "EC2"))
    )
    (comp (ref "U$2")
      (value "EC2")
      (footprint "eagle-import:DPDT_2.54")
      (libsource (lib "eagle-import") (part "EC2"))
    )
    (comp (ref "U$3")
      (value "EC2")
      (footprint "eagle-import:DPDT_2.54")
      (libsource (lib "eagle-import") (part "EC2"))
    )
    (comp (ref "C16")
      (value "1u")
      (footprint "eagle-import:C0805")
      (libsource (lib "eagle-import") (part "C-USC0805"))
    )
    (comp (ref "C20")
      (value "1u")
      (footprint "eagle-import:C0805")
      (libsource (lib "eagle-import") (part "C-USC0805"))
    )
    (comp (ref "C21")
      (value "1u")
      (footprint "eagle-import:C0603")
      (libsource (lib "eagle-import") (part "C-USC0603"))
    )
    (comp (ref "C33")
      (value "0.001u")
      (footprint "eagle-import:C0805")
      (libsource (lib "eagle-import") (part "C-USC0805"))
    )
    (comp (ref "C34")
      (value "0.001u")
      (footprint "eagle-import:C0805")
      (libsource (lib "eagle-import") (part "C-USC0805"))
    )
    (comp (ref "C35")
      (value "0.001u")
      (footprint "eagle-import:C0805")
      (libsource (lib "eagle-import") (part "C-USC0805"))
    )
    (comp (ref "C36")
      (value "0.001u")
      (footprint "eagle-import:C0805")
      (libsource (lib "eagle-import") (part "C-USC0805"))
    )
    (comp (ref "D13")
      (value "RED")
      (footprint "eagle-import:LED-0603")
      (libsource (lib "eagle-import") (part "LED-RED0603"))
    )
    (comp (ref "JP2")
      (value "PINHD-1X5")
      (footprint "eagle-import:1X05")
      (libsource (lib "eagle-import") (part "PINHD-1X5"))
    )
    (comp (ref "R7")
      (value "50k")
      (footprint "eagle-import:R0603")
      (libsource (lib "eagle-import") (part "R-US_R0603"))
    )
    (comp (ref "R28")
      (value "10k")
      (footprint "eagle-import:R0603")
      (libsource (lib "eagle-import") (part "R-US_R0603"))
    )
    (comp (ref "R29")
      (value "10k")
      (footprint "eagle-import:R0603")
      (libsource (lib "eagle-import") (part "R-US_R0603"))
    )
    (comp (ref "R47")
      (value "10k")
      (footprint "eagle-import:R0603")
      (libsource (lib "eagle-import") (part "R-US_R0603"))
    )
    (comp (ref "R48")
      (value "10k")
      (footprint "eagle-import:R0603")
      (libsource (lib "eagle-import") (part "R-US_R0603"))
    )
    (comp (ref "R57")
      (value "10")
      (footprint "eagle-import:R0603")
      (libsource (lib "eagle-import") (part "R-US_R0603"))
    )
    (comp (ref "R58")
      (value "10k")
      (footprint "eagle-import:R0603")
      (libsource (lib "eagle-import") (part "R-US_R0603"))
    )
    (comp (ref "R59")
      (value "10")
      (footprint "eagle-import:R0603")
      (libsource (lib "eagle-import") (part "R-US_R0603"))
    )
    (comp (ref "R60")
      (value "10k")
      (footprint "eagle-import:R0603")
      (libsource (lib "eagle-import") (part "R-US_R0603"))
    )
    (comp (ref "R61")
      (value "10")
      (footprint "eagle-import:R0603")
      (libsource (lib "eagle-import") (part "R-US_R0603"))
    )
    (comp (ref "R62")
      (value "10k")
      (footprint "eagle-import:R0603")
      (libsource (lib "eagle-import") (part "R-US_R0603"))
    )
    (comp (ref "R63")
      (value "10")
      (footprint "eagle-import:R0603")
      (libsource (lib "eagle-import") (part "R-US_R0603"))
    )
    (comp (ref "R64")
      (value "10k")
      (footprint "eagle-import:R0603")
      (libsource (lib "eagle-import") (part "R-US_R0603"))
    )
    (comp (ref "R65")
      (value "1k")
      (footprint "eagle-import:R0603")
      (libsource (lib "eagle-import") (part "R-US_R0603"))
    )
    (comp (ref "R66")
      (value "1k")
      (footprint "eagle-import:R0603")
      (libsource (lib "eagle-import") (part "R-US_R0603"))
    )
    (comp (ref "R67")
      (value "1k")
      (footprint "eagle-import:R0603")
      (libsource (lib "eagle-import") (part "R-US_R0603"))
    )
    (comp (ref "R68")
      (value "1k")
      (footprint "eagle-import:R0603")
      (libsource (lib "eagle-import") (part "R-US_R0603"))
    )
    (comp (ref "U$12")
      (value "MCP4018")
      (footprint "eagle-import:SOT23-6")
      (libsource (lib "eagle-import") (part "MCP4018"))
    )
    (comp (ref "U$18")
      (value "LMV321L")
      (footprint "eagle-import:SOT23-5")
      (libsource (lib "eagle-import") (part "LMV321L"))
    )
    (comp (ref "U$36")
      (value "BZT52C5V6")
      (footprint "eagle-import:SOD-123")
      (libsource (lib "eagle-import") (part "BZT52C"))
    )
    (comp (ref "U$37")
      (value "BZT52C5V6")
      (footprint "eagle-import:SOD-123")
      (libsource (lib "eagle-import") (part "BZT52C"))
    )
    (comp (ref "U$38")
      (value "BZT52C5V6")
      (footprint "eagle-import:SOD-123")
      (libsource (lib "eagle-import") (part "BZT52C"))
    )
    (comp (ref "U$39")
      (value "BZT52C5V6")
      (footprint "eagle-import:SOD-123")
      (libsource (lib "eagle-import") (part "BZT52C"))
    )
    (comp (ref "U2")
      (value "STM32F103CBT6")
      (footprint "eagle-import:QFP50P900X900X160-48N")
      (libsource (lib "eagle-import") (part "STM32F103CBT6"))
    )
    (comp (ref "Q18")
      (value "DMN6140L-7")
      (footprint "eagle-import:SOT23")
      (libsource (lib "eagle-import") (part "DMN6140L-7"))
    )
    (comp (ref "Q20")
      (value "DMN6140L-7")
      (footprint "eagle-import:SOT23")
      (libsource (lib "eagle-import") (part "DMN6140L-7"))
    )
    (comp (ref "Q21")
      (value "DMN6140L-7")
      (footprint "eagle-import:SOT23")
      (libsource (lib "eagle-import") (part "DMN6140L-7"))
    )
    (comp (ref "R30")
      (value "10k")
      (footprint "eagle-import:R0603")
      (libsource (lib "eagle-import") (part "R-US_R0603"))
    )
    (comp (ref "R31")
      (value "10k")
      (footprint "eagle-import:R0603")
      (libsource (lib "eagle-import") (part "R-US_R0603"))
    )
    (comp (ref "R32")
      (value "10k")
      (footprint "eagle-import:R0603")
      (libsource (lib "eagle-import") (part "R-US_R0603"))
    )
    (comp (ref "AIR")
      (value "505575-02")
      (footprint "eagle-import:505575-02")
      (libsource (lib "eagle-import") (part "505575-02"))
    )
    (comp (ref "C22")
      (value "0.1u")
      (footprint "eagle-import:C0805")
      (libsource (lib "eagle-import") (part "C-USC0805"))
    )
    (comp (ref "C23")
      (value "0.1u")
      (footprint "eagle-import:C0805")
      (libsource (lib "eagle-import") (part "C-USC0805"))
    )
    (comp (ref "C26")
      (value "0.1u")
      (footprint "eagle-import:C0805")
      (libsource (lib "eagle-import") (part "C-USC0805"))
    )
    (comp (ref "C29")
      (value "0.1u")
      (footprint "eagle-import:C0805")
      (libsource (lib "eagle-import") (part "C-USC0805"))
    )
    (comp (ref "C30")
      (value "0.1u")
      (footprint "eagle-import:C0805")
      (libsource (lib "eagle-import") (part "C-USC0805"))
    )
    (comp (ref "C31")
      (value "0.001u")
      (footprint "eagle-import:C0805")
      (libsource (lib "eagle-import") (part "C-USC0805"))
    )
    (comp (ref "C32")
      (value "0.1u")
      (footprint "eagle-import:C0805")
      (libsource (lib "eagle-import") (part "C-USC0805"))
    )
    (comp (ref "C37")
      (value "0.1u")
      (footprint "eagle-import:C0603")
      (libsource (lib "eagle-import") (part "resistor_348_C-USC0603"))
    )
    (comp (ref "C38")
      (value "0.1u")
      (footprint "eagle-import:C0603")
      (libsource (lib "eagle-import") (part "resistor_348_C-USC0603"))
    )
    (comp (ref "C39")
      (value "0.1u")
      (footprint "eagle-import:C0603")
      (libsource (lib "eagle-import") (part "resistor_348_C-USC0603"))
    )
    (comp (ref "C40")
      (value "0.001u")
      (footprint "eagle-import:C0805")
      (libsource (lib "eagle-import") (part "C-USC0805"))
    )
    (comp (ref "C41")
      (value "0.001u")
      (footprint "eagle-import:C0805")
      (libsource (lib "eagle-import") (part "C-USC0805"))
    )
    (comp (ref "C42")
      (value "0.1u")
      (footprint "eagle-import:C0603")
      (libsource (lib "eagle-import") (part "resistor_348_C-USC0603"))
    )
    (comp (ref "C43")
      (value "0.1u")
      (footprint "eagle-import:C0603")
      (libsource (lib "eagle-import") (part "resistor_348_C-USC0603"))
    )
    (comp (ref "CAN")
      (value "505575-02")
      (footprint "eagle-import:505575-02")
      (libsource (lib "eagle-import") (part "505575-02"))
    )
    (comp (ref "CURRENT_SENSE_SUPPLY")
      (value "505575-02")
      (footprint "eagle-import:505575-02")
      (libsource (lib "eagle-import") (part "505575-02"))
    )
    (comp (ref "ENABLE")
      (value "505575-02")
      (footprint "eagle-import:505575-02")
      (libsource (lib "eagle-import") (part "505575-02"))
    )
    (comp (ref "FAULT_IN")
      (value "505575-05")
      (footprint "eagle-import:505575-05")
      (libsource (lib "eagle-import") (part "505575-05"))
    )
    (comp (ref "FAULT_STAT")
      (value "505575-03")
      (footprint "eagle-import:505575-03")
      (libsource (lib "eagle-import") (part "505575-03"))
    )
    (comp (ref "H1")
      (value "MOUNT-PAD-ROUND3.0")
      (footprint "eagle-import:3,0-PAD")
      (libsource (lib "eagle-import") (part "MOUNT-PAD-ROUND3.0"))
    )
    (comp (ref "H2")
      (value "MOUNT-PAD-ROUND3.0")
      (footprint "eagle-import:3,0-PAD")
      (libsource (lib "eagle-import") (part "MOUNT-PAD-ROUND3.0"))
    )
    (comp (ref "H3")
      (value "MOUNT-PAD-ROUND3.0")
      (footprint "eagle-import:3,0-PAD")
      (libsource (lib "eagle-import") (part "MOUNT-PAD-ROUND3.0"))
    )
    (comp (ref "H4")
      (value "MOUNT-PAD-ROUND3.0")
      (footprint "eagle-import:3,0-PAD")
      (libsource (lib "eagle-import") (part "MOUNT-PAD-ROUND3.0"))
    )
    (comp (ref "HALL_SENSOR_INPUT")
      (value "505575-04")
      (footprint "eagle-import:505575-04")
      (libsource (lib "eagle-import") (part "505575-04"))
    )
    (comp (ref "LIGHTING")
      (value "505575-05")
      (footprint "eagle-import:505575-05")
      (libsource (lib "eagle-import") (part "505575-05"))
    )
    (comp (ref "POWER")
      (value "505575-02")
      (footprint "eagle-import:505575-02")
      (libsource (lib "eagle-import") (part "505575-02"))
    )
    (comp (ref "POWER_ANALOG")
      (value "505575-02")
      (footprint "eagle-import:505575-02")
      (libsource (lib "eagle-import") (part "505575-02"))
    )
    (comp (ref "Q7")
      (value "DMN6140L-7")
      (footprint "eagle-import:SOT23")
      (libsource (lib "eagle-import") (part "DMN6140L-7"))
    )
    (comp (ref "R10")
      (value "10")
      (footprint "eagle-import:R0603")
      (libsource (lib "eagle-import") (part "R-US_R0603"))
    )
    (comp (ref "R33")
      (value "100")
      (footprint "eagle-import:R0603")
      (libsource (lib "eagle-import") (part "R-US_R0603"))
    )
    (comp (ref "R34")
      (value "100k")
      (footprint "eagle-import:R0603")
      (libsource (lib "eagle-import") (part "R-US_R0603"))
    )
    (comp (ref "R35")
      (value "1k")
      (footprint "eagle-import:R0603")
      (libsource (lib "eagle-import") (part "R-US_R0603"))
    )
    (comp (ref "R37")
      (value "100")
      (footprint "eagle-import:R0603")
      (libsource (lib "eagle-import") (part "R-US_R0603"))
    )
    (comp (ref "R38")
      (value "100k")
      (footprint "eagle-import:R0603")
      (libsource (lib "eagle-import") (part "R-US_R0603"))
    )
    (comp (ref "R41")
      (value "100")
      (footprint "eagle-import:R0603")
      (libsource (lib "eagle-import") (part "R-US_R0603"))
    )
    (comp (ref "R42")
      (value "100k")
      (footprint "eagle-import:R0603")
      (libsource (lib "eagle-import") (part "R-US_R0603"))
    )
    (comp (ref "R45")
      (value "10k")
      (footprint "eagle-import:R0603")
      (libsource (lib "eagle-import") (part "R-US_R0603"))
    )
    (comp (ref "R46")
      (value "10k")
      (footprint "eagle-import:R0603")
      (libsource (lib "eagle-import") (part "R-US_R0603"))
    )
    (comp (ref "R49")
      (value "10")
      (footprint "eagle-import:R0603")
      (libsource (lib "eagle-import") (part "R-US_R0603"))
    )
    (comp (ref "R50")
      (value "100k")
      (footprint "eagle-import:R0603")
      (libsource (lib "eagle-import") (part "R-US_R0603"))
    )
    (comp (ref "R51")
      (value "10")
      (footprint "eagle-import:R0603")
      (libsource (lib "eagle-import") (part "R-US_R0603"))
    )
    (comp (ref "R52")
      (value "100k")
      (footprint "eagle-import:R0603")
      (libsource (lib "eagle-import") (part "R-US_R0603"))
    )
    (comp (ref "R53")
      (value "10")
      (footprint "eagle-import:R0603")
      (libsource (lib "eagle-import") (part "R-US_R0603"))
    )
    (comp (ref "R54")
      (value "10k")
      (footprint "eagle-import:R0603")
      (libsource (lib "eagle-import") (part "R-US_R0603"))
    )
    (comp (ref "R55")
      (value "100")
      (footprint "eagle-import:R0603")
      (libsource (lib "eagle-import") (part "R-US_R0603"))
    )
    (comp (ref "R56")
      (value "100k")
      (footprint "eagle-import:R0603")
      (libsource (lib "eagle-import") (part "R-US_R0603"))
    )
    (comp (ref "R69")
      (value "10k")
      (footprint "eagle-import:R0603")
      (libsource (lib "eagle-import") (part "R-US_R0603"))
    )
    (comp (ref "R70")
      (value "10k")
      (footprint "eagle-import:R0603")
      (libsource (lib "eagle-import") (part "R-US_R0603"))
    )
    (comp (ref "R71")
      (value "15k")
      (footprint "eagle-import:R0603")
      (libsource (lib "eagle-import") (part "R-US_R0603"))
    )
    (comp (ref "R72")
      (value "15k")
      (footprint "eagle-import:R0603")
      (libsource (lib "eagle-import") (part "R-US_R0603"))
    )
    (comp (ref "R73")
      (value "15k")
      (footprint "eagle-import:R0603")
      (libsource (lib "eagle-import") (part "R-US_R0603"))
    )
    (comp (ref "R74")
      (value "10k")
      (footprint "eagle-import:R0603")
      (libsource (lib "eagle-import") (part "R-US_R0603"))
    )
    (comp (ref "R75")
      (value "10k")
      (footprint "eagle-import:R0603")
      (libsource (lib "eagle-import") (part "R-US_R0603"))
    )
    (comp (ref "R76")
      (value "15k")
      (footprint "eagle-import:R0603")
      (libsource (lib "eagle-import") (part "R-US_R0603"))
    )
    (comp (ref "R77")
      (value "1k")
      (footprint "eagle-import:R0603")
      (libsource (lib "eagle-import") (part "R-US_R0603"))
    )
    (comp (ref "R78")
      (value "10")
      (footprint "eagle-import:R0603")
      (libsource (lib "eagle-import") (part "R-US_R0603"))
    )
    (comp (ref "R79")
      (value "10k")
      (footprint "eagle-import:R0603")
      (libsource (lib "eagle-import") (part "R-US_R0603"))
    )
    (comp (ref "R80")
      (value "10k")
      (footprint "eagle-import:R0603")
      (libsource (lib "eagle-import") (part "R-US_R0603"))
    )
    (comp (ref "R81")
      (value "15k")
      (footprint "eagle-import:R0603")
      (libsource (lib "eagle-import") (part "R-US_R0603"))
    )
    (comp (ref "R82")
      (value "1k")
      (footprint "eagle-import:R0603")
      (libsource (lib "eagle-import") (part "R-US_R0603"))
    )
    (comp (ref "SOFT_FAULT_STAT")
      (value "505575-02")
      (footprint "eagle-import:505575-02")
      (libsource (lib "eagle-import") (part "505575-02"))
    )
    (comp (ref "THROTTLE_TC")
      (value "505575-05")
      (footprint "eagle-import:505575-05")
      (libsource (lib "eagle-import") (part "505575-05"))
    )
    (comp (ref "U$8")
      (value "0805_INDUCTOR")
      (footprint "eagle-import:L0805")
      (libsource (lib "eagle-import") (part "0805_INDUCTOR"))
    )
    (comp (ref "U$13")
      (value "LMV321L")
      (footprint "eagle-import:SOT23-5")
      (libsource (lib "eagle-import") (part "LMV321L"))
    )
    (comp (ref "U$14")
      (value "BZT52C5V6")
      (footprint "eagle-import:SOD-123")
      (libsource (lib "eagle-import") (part "BZT52C"))
    )
    (comp (ref "U$15")
      (value "LMV321L")
      (footprint "eagle-import:SOT23-5")
      (libsource (lib "eagle-import") (part "LMV321L"))
    )
    (comp (ref "U$19")
      (value "BZT52C5V6")
      (footprint "eagle-import:SOD-123")
      (libsource (lib "eagle-import") (part "BZT52C"))
    )
    (comp (ref "U$21")
      (value "BZT52C13")
      (footprint "eagle-import:SOD-123")
      (libsource (lib "eagle-import") (part "BZT52C"))
    )
    (comp (ref "U$22")
      (value "LMV321L")
      (footprint "eagle-import:SOT23-5")
      (libsource (lib "eagle-import") (part "LMV321L"))
    )
    (comp (ref "U$23")
      (value "LMV321L")
      (footprint "eagle-import:SOT23-5")
      (libsource (lib "eagle-import") (part "LMV321L"))
    )
    (comp (ref "U$24")
      (value "LMV321L")
      (footprint "eagle-import:SOT23-5")
      (libsource (lib "eagle-import") (part "LMV321L"))
    )
    (comp (ref "U$25")
      (value "BZT52C13")
      (footprint "eagle-import:SOD-123")
      (libsource (lib "eagle-import") (part "BZT52C"))
    )
    (comp (ref "U$26")
      (value "BZT52C13")
      (footprint "eagle-import:SOD-123")
      (libsource (lib "eagle-import") (part "BZT52C"))
    )
    (comp (ref "U$29")
      (value "BZT52C13")
      (footprint "eagle-import:SOD-123")
      (libsource (lib "eagle-import") (part "BZT52C"))
    )
    (comp (ref "U$32")
      (value "BZT52C5V6")
      (footprint "eagle-import:SOD-123")
      (libsource (lib "eagle-import") (part "BZT52C"))
    )
    (comp (ref "U$33")
      (value "BZT52C5V6")
      (footprint "eagle-import:SOD-123")
      (libsource (lib "eagle-import") (part "BZT52C"))
    )
    (comp (ref "U$34")
      (value "BZT52C5V6")
      (footprint "eagle-import:SOD-123")
      (libsource (lib "eagle-import") (part "BZT52C"))
    )
    (comp (ref "C10")
      (value "220u")
      (footprint "eagle-import:E2,5-7")
      (libsource (lib "eagle-import") (part "CPOL-USE2.5-7"))
    )
    (comp (ref "C11")
      (value "2.2u")
      (footprint "eagle-import:C0805")
      (libsource (lib "eagle-import") (part "C-USC0805"))
    )
    (comp (ref "C12")
      (value "4.7u")
      (footprint "eagle-import:C0805")
      (libsource (lib "eagle-import") (part "C-USC0805"))
    )
    (comp (ref "C13")
      (value "4.7u")
      (footprint "eagle-import:C0805")
      (libsource (lib "eagle-import") (part "C-USC0805"))
    )
    (comp (ref "C14")
      (value "2.2u")
      (footprint "eagle-import:C0805")
      (libsource (lib "eagle-import") (part "C-USC0805"))
    )
    (comp (ref "D11")
      (value "GREEN")
      (footprint "eagle-import:LED-0603")
      (libsource (lib "eagle-import") (part "LED-GREEN0603"))
    )
    (comp (ref "D12")
      (value "GREEN")
      (footprint "eagle-import:LED-0603")
      (libsource (lib "eagle-import") (part "LED-GREEN0603"))
    )
    (comp (ref "FUSE")
      (value "MINI297-3568")
      (footprint "eagle-import:3568")
      (libsource (lib "eagle-import") (part "MINI297-3568"))
    )
    (comp (ref "L4")
      (value "10u")
      (footprint "eagle-import:INDUCTOR_5X5MM_NR5040_NOTHERMALS")
      (libsource (lib "eagle-import") (part "INDUCTORNR5040"))
    )
    (comp (ref "R2")
      (value "100")
      (footprint "eagle-import:R0603")
      (libsource (lib "eagle-import") (part "R-US_R0603"))
    )
    (comp (ref "R4")
      (value "100")
      (footprint "eagle-import:R0603")
      (libsource (lib "eagle-import") (part "R-US_R0603"))
    )
    (comp (ref "U$9")
      (value "SPX1117M3-L-3-3")
      (footprint "eagle-import:SOT223")
      (libsource (lib "eagle-import") (part "SPX1117M3-L-3-3"))
    )
    (comp (ref "U$10")
      (value "SPX1117M3-L-5-0")
      (footprint "eagle-import:SOT223")
      (libsource (lib "eagle-import") (part "SPX1117M3-L-5-0"))
    )
    (comp (ref "Q8")
      (value "DMN6140L-7")
      (footprint "eagle-import:SOT23")
      (libsource (lib "eagle-import") (part "DMN6140L-7"))
    )
    (comp (ref "Q10")
      (value "DMN6140L-7")
      (footprint "eagle-import:SOT23")
      (libsource (lib "eagle-import") (part "DMN6140L-7"))
    )
    (comp (ref "Q13")
      (value "DMN6140L-7")
      (footprint "eagle-import:SOT23")
      (libsource (lib "eagle-import") (part "DMN6140L-7"))
    )
    (comp (ref "R3")
      (value "10k")
      (footprint "eagle-import:R0603")
      (libsource (lib "eagle-import") (part "resistor_348_R-US_R0603"))
    )
    (comp (ref "R23")
      (value "10k")
      (footprint "eagle-import:R0603")
      (libsource (lib "eagle-import") (part "resistor_348_R-US_R0603"))
    )
    (comp (ref "U$7")
      (value "SN74LVC1G04DBVR")
      (footprint "eagle-import:SOT23-5L")
      (libsource (lib "eagle-import") (part "SN74LVC1G04DBVR"))
    )
    (comp (ref "R9")
      (value "1k")
      (footprint "eagle-import:R0603")
      (libsource (lib "eagle-import") (part "R-US_R0603"))
    )
    (comp (ref "U$4")
      (value "DNBT8105")
      (footprint "eagle-import:SOT23-3")
      (libsource (lib "eagle-import") (part "DNBT8105"))
    )
  )
  (nets
    (net (code "1") (name "+3V3") (class "Default")
      (node (ref "C11") (pin "1") (pinfunction "1_1") (pintype "passive"))
      (node (ref "C15") (pin "1") (pinfunction "1_1") (pintype "passive"))
      (node (ref "C16") (pin "1") (pinfunction "1_1") (pintype "passive"))
      (node (ref "C19") (pin "1") (pinfunction "1_1") (pintype "passive"))
      (node (ref "C20") (pin "1") (pinfunction "1_1") (pintype "passive"))
      (node (ref "D11") (pin "A") (pinfunction "A_A") (pintype "passive"))
      (node (ref "JP1") (pin "1") (pinfunction "1_1") (pintype "passive"))
      (node (ref "JP2") (pin "1") (pinfunction "1_1") (pintype "passive"))
      (node (ref "R12") (pin "2") (pinfunction "2_2") (pintype "passive"))
      (node (ref "R13") (pin "2") (pinfunction "2_2") (pintype "passive"))
      (node (ref "R14") (pin "2") (pinfunction "2_2") (pintype "passive"))
      (node (ref "R23") (pin "2") (pinfunction "2_2") (pintype "passive"))
      (node (ref "R26") (pin "1") (pinfunction "1_1") (pintype "passive"))
      (node (ref "R27") (pin "1") (pinfunction "1_1") (pintype "passive"))
      (node (ref "R28") (pin "1") (pinfunction "1_1") (pintype "passive"))
      (node (ref "R29") (pin "1") (pinfunction "1_1") (pintype "passive"))
      (node (ref "R74") (pin "2") (pinfunction "2_2") (pintype "passive"))
      (node (ref "U$11") (pin "5") (pinfunction "VIO_5") (pintype "bidirectional"))
      (node (ref "U$7") (pin "5") (pinfunction "V+_5") (pintype "bidirectional"))
      (node (ref "U$9") (pin "2") (pinfunction "VOUT_2") (pintype "output"))
      (node (ref "U$9") (pin "4") (pinfunction "VOUT_4") (pintype "output"))
      (node (ref "U1") (pin "24") (pinfunction "VDD_1_24") (pintype "bidirectional"))
      (node (ref "U1") (pin "36") (pinfunction "VDD_2_36") (pintype "power_in"))
      (node (ref "U1") (pin "48") (pinfunction "VDD_3_48") (pintype "power_in"))
      (node (ref "U1") (pin "9") (pinfunction "VDDA_9") (pintype "power_in"))
      (node (ref "U2") (pin "24") (pinfunction "VDD_1_24") (pintype "bidirectional"))
      (node (ref "U2") (pin "36") (pinfunction "VDD_2_36") (pintype "power_in"))
      (node (ref "U2") (pin "48") (pinfunction "VDD_3_48") (pintype "power_in"))
      (node (ref "U2") (pin "9") (pinfunction "VDDA_9") (pintype "power_in"))
    )
    (net (code "2") (name "+5V") (class "Default")
      (node (ref "BRAKE") (pin "A") (pinfunction "A_A") (pintype "passive"))
      (node (ref "C1") (pin "1") (pinfunction "1_1") (pintype "passive"))
      (node (ref "C14") (pin "1") (pinfunction "1_1") (pintype "passive"))
      (node (ref "C24") (pin "1") (pinfunction "1_1") (pintype "passive"))
      (node (ref "C27") (pin "1") (pinfunction "1_1") (pintype "passive"))
      (node (ref "C28") (pin "1") (pinfunction "1_1") (pintype "passive"))
      (node (ref "C37") (pin "1") (pinfunction "1_1") (pintype "passive"))
      (node (ref "C38") (pin "1") (pinfunction "1_1") (pintype "passive"))
      (node (ref "C39") (pin "1") (pinfunction "1_1") (pintype "passive"))
      (node (ref "C42") (pin "1") (pinfunction "1_1") (pintype "passive"))
      (node (ref "C43") (pin "1") (pinfunction "1_1") (pintype "passive"))
      (node (ref "C44") (pin "1") (pinfunction "1_1") (pintype "passive"))
      (node (ref "C45") (pin "1") (pinfunction "1_1") (pintype "passive"))
      (node (ref "C46") (pin "1") (pinfunction "1_1") (pintype "passive"))
      (node (ref "CURR") (pin "A") (pinfunction "A_A") (pintype "passive"))
      (node (ref "CURRENT_SENSE_SUPPLY") (pin "1") (pinfunction "1_1") (pintype "bidirectional"))
      (node (ref "D12") (pin "A") (pinfunction "A_A") (pintype "passive"))
      (node (ref "R11") (pin "2") (pinfunction "2_2") (pintype "passive"))
      (node (ref "R35") (pin "2") (pinfunction "2_2") (pintype "passive"))
      (node (ref "R39") (pin "2") (pinfunction "2_2") (pintype "passive"))
      (node (ref "R47") (pin "1") (pinfunction "1_1") (pintype "passive"))
      (node (ref "R48") (pin "1") (pinfunction "1_1") (pintype "passive"))
      (node (ref "R65") (pin "2") (pinfunction "2_2") (pintype "passive"))
      (node (ref "R66") (pin "2") (pinfunction "2_2") (pintype "passive"))
      (node (ref "R67") (pin "2") (pinfunction "2_2") (pintype "passive"))
      (node (ref "R68") (pin "2") (pinfunction "2_2") (pintype "passive"))
      (node (ref "R77") (pin "2") (pinfunction "2_2") (pintype "passive"))
      (node (ref "R8") (pin "2") (pinfunction "2_2") (pintype "passive"))
      (node (ref "R82") (pin "2") (pinfunction "2_2") (pintype "passive"))
      (node (ref "U$10") (pin "2") (pinfunction "VOUT_2") (pintype "output"))
      (node (ref "U$10") (pin "4") (pinfunction "VOUT_4") (pintype "output"))
      (node (ref "U$11") (pin "3") (pinfunction "VDD_3") (pintype "bidirectional"))
      (node (ref "U$13") (pin "5") (pinfunction "VDD_5") (pintype "bidirectional"))
      (node (ref "U$15") (pin "5") (pinfunction "VDD_5") (pintype "bidirectional"))
      (node (ref "U$16") (pin "5") (pinfunction "VDD_5") (pintype "bidirectional"))
      (node (ref "U$17") (pin "5") (pinfunction "VDD_5") (pintype "bidirectional"))
      (node (ref "U$20") (pin "5") (pinfunction "VDD_5") (pintype "bidirectional"))
      (node (ref "U$22") (pin "5") (pinfunction "VDD_5") (pintype "bidirectional"))
      (node (ref "U$23") (pin "5") (pinfunction "VDD_5") (pintype "bidirectional"))
      (node (ref "U$24") (pin "5") (pinfunction "VDD_5") (pintype "bidirectional"))
      (node (ref "U$27") (pin "5") (pinfunction "VDD_5") (pintype "power_in"))
      (node (ref "U$28") (pin "P14") (pinfunction "VDD_P14") (pintype "bidirectional"))
      (node (ref "U$30") (pin "5") (pinfunction "VDD_5") (pintype "bidirectional"))
      (node (ref "U$31") (pin "5") (pinfunction "VDD_5") (pintype "bidirectional"))
      (node (ref "U$5") (pin "5") (pinfunction "VDD_5") (pintype "bidirectional"))
    )
    (net (code "3") (name "+12V") (class "Default")
      (node (ref "C10") (pin "+") (pinfunction "+_+") (pintype "passive"))
      (node (ref "C12") (pin "1") (pinfunction "1_1") (pintype "passive"))
      (node (ref "C13") (pin "1") (pinfunction "1_1") (pintype "passive"))
      (node (ref "L4") (pin "P$2") (pinfunction "2_P$2") (pintype "passive"))
      (node (ref "Q11") (pin "2") (pinfunction "S_2") (pintype "passive"))
      (node (ref "Q15") (pin "2") (pinfunction "S_2") (pintype "passive"))
      (node (ref "Q6") (pin "2") (pinfunction "S_2") (pintype "passive"))
      (node (ref "R25") (pin "2") (pinfunction "2_2") (pintype "passive"))
      (node (ref "R5") (pin "2") (pinfunction "2_2") (pintype "passive"))
      (node (ref "U$1") (pin "$P5") (pinfunction "$P5_$P5") (pintype "passive"))
      (node (ref "U$10") (pin "3") (pinfunction "VIN_3") (pintype "input"))
      (node (ref "U$2") (pin "$P5") (pinfunction "$P5_$P5") (pintype "passive"))
      (node (ref "U$3") (pin "$P5") (pinfunction "$P5_$P5") (pintype "passive"))
      (node (ref "U$6") (pin "POS") (pinfunction "A_POS") (pintype "input"))
      (node (ref "U$9") (pin "3") (pinfunction "VIN_3") (pintype "input"))
    )
    (net (code "4") (name "AGND") (class "Default")
      (node (ref "C21") (pin "2") (pinfunction "2_2") (pintype "passive"))
      (node (ref "POWER_ANALOG") (pin "2") (pinfunction "2_2") (pintype "bidirectional"))
      (node (ref "R7") (pin "1") (pinfunction "1_1") (pintype "passive"))
      (node (ref "U$12") (pin "2") (pinfunction "VSS_2") (pintype "passive"))
      (node (ref "U$18") (pin "2") (pinfunction "GND_2") (pintype "bidirectional"))
      (node (ref "U$8") (pin "1") (pinfunction "1_1") (pintype "passive"))
    )
    (net (code "5") (name "AIR_IN") (class "Default")
      (node (ref "AIR") (pin "2") (pinfunction "2_2") (pintype "bidirectional"))
      (node (ref "U$1") (pin "$P9") (pinfunction "$P9_$P9") (pintype "passive"))
    )
    (net (code "6") (name "AIR_OUT") (class "Default")
      (node (ref "AIR") (pin "1") (pinfunction "1_1") (pintype "bidirectional"))
      (node (ref "U$3") (pin "$P8") (pinfunction "$P8_$P8") (pintype "passive"))
    )
    (net (code "7") (name "ANALOG_5V") (class "Default")
      (node (ref "C21") (pin "1") (pinfunction "1_1") (pintype "passive"))
      (node (ref "POWER_ANALOG") (pin "1") (pinfunction "1_1") (pintype "bidirectional"))
      (node (ref "U$12") (pin "1") (pinfunction "VDD_1") (pintype "passive"))
      (node (ref "U$18") (pin "5") (pinfunction "VDD_5") (pintype "bidirectional"))
    )
    (net (code "8") (name "APPS_EN") (class "Default")
      (node (ref "Q20") (pin "1") (pinfunction "G_1") (pintype "passive"))
      (node (ref "R30") (pin "2") (pinfunction "2_2") (pintype "passive"))
      (node (ref "SOFT_FAULT_STAT") (pin "1") (pinfunction "1_1") (pintype "bidirectional"))
      (node (ref "U1") (pin "40") (pinfunction "PB4_40") (pintype "bidirectional"))
    )
    (net (code "9") (name "BRAKE_LIGHT-") (class "Default")
      (node (ref "LIGHTING") (pin "4") (pinfunction "4_4") (pintype "bidirectional"))
      (node (ref "U$4") (pin "3") (pinfunction "C_3") (pintype "passive"))
    )
    (net (code "10") (name "BRAKE_LIGHT_EN") (class "Default")
      (node (ref "R9") (pin "1") (pinfunction "1_1") (pintype "passive"))
      (node (ref "U1") (pin "26") (pinfunction "PB13_26") (pintype "bidirectional"))
    )
    (net (code "11") (name "BRAKE_POS") (class "Default")
      (node (ref "R10") (pin "1") (pinfunction "1_1") (pintype "passive"))
      (node (ref "THROTTLE_TC") (pin "4") (pinfunction "4_4") (pintype "bidirectional"))
    )
    (net (code "12") (name "BRAKE_POS_F") (class "Default")
      (node (ref "R75") (pin "2") (pinfunction "2_2") (pintype "passive"))
      (node (ref "U$13") (pin "3") (pinfunction "-IN_3") (pintype "input"))
      (node (ref "U$13") (pin "4") (pinfunction "OUT_4") (pintype "output"))
    )
    (net (code "13") (name "BRAKE_POS_F_3_3") (class "Default")
      (node (ref "R75") (pin "1") (pinfunction "1_1") (pintype "passive"))
      (node (ref "R76") (pin "2") (pinfunction "2_2") (pintype "passive"))
      (node (ref "U1") (pin "11") (pinfunction "PA1_11") (pintype "bidirectional"))
    )
    (net (code "14") (name "BRAKE_PRESSURE") (class "Default")
      (node (ref "FAULT_IN") (pin "4") (pinfunction "4_4") (pintype "bidirectional"))
      (node (ref "R53") (pin "1") (pinfunction "1_1") (pintype "passive"))
    )
    (net (code "15") (name "BRAKE_PRESSURE_F") (class "Default")
      (node (ref "R70") (pin "2") (pinfunction "2_2") (pintype "passive"))
      (node (ref "U$24") (pin "3") (pinfunction "-IN_3") (pintype "input"))
      (node (ref "U$24") (pin "4") (pinfunction "OUT_4") (pintype "output"))
      (node (ref "U$30") (pin "4") (pinfunction "-IN_4") (pintype "input"))
      (node (ref "U$31") (pin "3") (pinfunction "+IN_3") (pintype "input"))
      (node (ref "U$5") (pin "3") (pinfunction "+IN_3") (pintype "input"))
    )
    (net (code "16") (name "BRAKE_PRESSURE_F_3_3") (class "Default")
      (node (ref "R70") (pin "1") (pinfunction "1_1") (pintype "passive"))
      (node (ref "R71") (pin "2") (pinfunction "2_2") (pintype "passive"))
      (node (ref "U1") (pin "10") (pinfunction "PA0-WKUP_10") (pintype "bidirectional"))
    )
    (net (code "17") (name "BRAKE_TH") (class "Default")
      (node (ref "BRAKE") (pin "W") (pinfunction "W_W") (pintype "bidirectional"))
      (node (ref "BTH1") (pin "TP") (pinfunction "TP_TP") (pintype "input"))
      (node (ref "U$5") (pin "4") (pinfunction "-IN_4") (pintype "input"))
    )
    (net (code "18") (name "BSPD_BP_OC") (class "Default")
      (node (ref "U$28") (pin "P2") (pinfunction "A0_P2") (pintype "bidirectional"))
      (node (ref "U$31") (pin "1") (pinfunction "OUT_1") (pintype "output"))
    )
    (net (code "19") (name "BSPD_BP_SC") (class "Default")
      (node (ref "U$28") (pin "P4") (pinfunction "C0_P4") (pintype "bidirectional"))
      (node (ref "U$30") (pin "1") (pinfunction "OUT_1") (pintype "output"))
    )
    (net (code "20") (name "BSPD_BRAKE_COND") (class "Default")
      (node (ref "C3") (pin "1") (pinfunction "1_1") (pintype "passive"))
      (node (ref "R1") (pin "1") (pinfunction "1_1") (pintype "passive"))
      (node (ref "U$27") (pin "2") (pinfunction "B_2") (pintype "input"))
    )
    (net (code "21") (name "BSPD_COND") (class "Default")
      (node (ref "Q12") (pin "1") (pinfunction "G_1") (pintype "passive"))
      (node (ref "R83") (pin "2") (pinfunction "2_2") (pintype "passive"))
      (node (ref "U$27") (pin "4") (pinfunction "Y_4") (pintype "output"))
    )
    (net (code "22") (name "BSPD_CS_OC") (class "Default")
      (node (ref "U$17") (pin "1") (pinfunction "OUT_1") (pintype "output"))
      (node (ref "U$28") (pin "P3") (pinfunction "B0_P3") (pintype "bidirectional"))
    )
    (net (code "23") (name "BSPD_CS_SC") (class "Default")
      (node (ref "U$16") (pin "1") (pinfunction "OUT_1") (pintype "output"))
      (node (ref "U$28") (pin "P5") (pinfunction "D0_P5") (pintype "bidirectional"))
    )
    (net (code "24") (name "BSPD_CURR_COND") (class "Default")
      (node (ref "C4") (pin "1") (pinfunction "1_1") (pintype "passive"))
      (node (ref "R36") (pin "1") (pinfunction "1_1") (pintype "passive"))
      (node (ref "U$27") (pin "1") (pinfunction "A_1") (pintype "input"))
    )
    (net (code "25") (name "BSPD_SENSOR_FAULT") (class "Default")
      (node (ref "Q14") (pin "1") (pinfunction "G_1") (pintype "passive"))
      (node (ref "U$28") (pin "P1") (pinfunction "Y0_P1") (pintype "bidirectional"))
    )
    (net (code "26") (name "BTSF_EN") (class "Default")
      (node (ref "Q18") (pin "1") (pinfunction "G_1") (pintype "passive"))
      (node (ref "R31") (pin "2") (pinfunction "2_2") (pintype "passive"))
      (node (ref "SOFT_FAULT_STAT") (pin "2") (pinfunction "2_2") (pintype "bidirectional"))
      (node (ref "U1") (pin "41") (pinfunction "PB5_41") (pintype "bidirectional"))
    )
    (net (code "27") (name "CANH") (class "Default")
      (node (ref "CAN") (pin "1") (pinfunction "1_1") (pintype "bidirectional"))
      (node (ref "D8") (pin "1") (pinfunction "1_1") (pintype "passive"))
      (node (ref "R20") (pin "2") (pinfunction "2_2") (pintype "passive"))
      (node (ref "R24") (pin "2") (pinfunction "2_2") (pintype "passive"))
      (node (ref "U$11") (pin "7") (pinfunction "CANH_7") (pintype "bidirectional"))
    )
    (net (code "28") (name "CANL") (class "Default")
      (node (ref "CAN") (pin "2") (pinfunction "2_2") (pintype "bidirectional"))
      (node (ref "D8") (pin "2") (pinfunction "2_2") (pintype "passive"))
      (node (ref "R19") (pin "2") (pinfunction "2_2") (pintype "passive"))
      (node (ref "R24") (pin "1") (pinfunction "1_1") (pintype "passive"))
      (node (ref "U$11") (pin "6") (pinfunction "CANL_6") (pintype "bidirectional"))
    )
    (net (code "29") (name "CAN_RX") (class "Default")
      (node (ref "U$11") (pin "4") (pinfunction "RX_4") (pintype "bidirectional"))
      (node (ref "U1") (pin "32") (pinfunction "PA11_32") (pintype "power_in"))
    )
    (net (code "30") (name "CAN_STBY") (class "Default")
      (node (ref "U$11") (pin "8") (pinfunction "STBY_8") (pintype "bidirectional"))
      (node (ref "U1") (pin "31") (pinfunction "PA10_31") (pintype "bidirectional"))
    )
    (net (code "31") (name "CAN_TX") (class "Default")
      (node (ref "U$11") (pin "1") (pinfunction "TX_1") (pintype "bidirectional"))
      (node (ref "U1") (pin "33") (pinfunction "PA12_33") (pintype "bidirectional"))
    )
    (net (code "32") (name "CURRENT_SENSE") (class "Default")
      (node (ref "FAULT_IN") (pin "5") (pinfunction "5_5") (pintype "bidirectional"))
      (node (ref "R44") (pin "2") (pinfunction "2_2") (pintype "passive"))
      (node (ref "R8") (pin "1") (pinfunction "1_1") (pintype "passive"))
    )
    (net (code "33") (name "CURRENT_SENSE_F") (class "Default")
      (node (ref "C25") (pin "1") (pinfunction "1_1") (pintype "passive"))
      (node (ref "R44") (pin "1") (pinfunction "1_1") (pintype "passive"))
      (node (ref "U$16") (pin "4") (pinfunction "-IN_4") (pintype "input"))
      (node (ref "U$17") (pin "3") (pinfunction "+IN_3") (pintype "input"))
      (node (ref "U$20") (pin "3") (pinfunction "+IN_3") (pintype "input"))
    )
    (net (code "34") (name "CURR_TH") (class "Default")
      (node (ref "CURR") (pin "W") (pinfunction "W_W") (pintype "bidirectional"))
      (node (ref "TTH1") (pin "TP") (pinfunction "TP_TP") (pintype "input"))
      (node (ref "U$20") (pin "4") (pinfunction "-IN_4") (pintype "input"))
    )
    (net (code "35") (name "DEBUG") (class "Default")
      (node (ref "D10") (pin "C") (pinfunction "C_C") (pintype "passive"))
      (node (ref "U1") (pin "2") (pinfunction "PC13-TAMPER-RTC_2") (pintype "bidirectional"))
    )
    (net (code "36") (name "DEBUG_TC") (class "Default")
      (node (ref "D13") (pin "C") (pinfunction "C_C") (pintype "passive"))
      (node (ref "U2") (pin "2") (pinfunction "PC13-TAMPER-RTC_2") (pintype "bidirectional"))
    )
    (net (code "37") (name "ENABLE_IN") (class "Default")
      (node (ref "ENABLE") (pin "2") (pinfunction "2_2") (pintype "bidirectional"))
      (node (ref "Q21") (pin "2") (pinfunction "S_2") (pintype "passive"))
    )
    (net (code "38") (name "ENABLE_OUT") (class "Default")
      (node (ref "ENABLE") (pin "1") (pinfunction "1_1") (pintype "bidirectional"))
      (node (ref "Q20") (pin "3") (pinfunction "D_3") (pintype "passive"))
    )
    (net (code "39") (name "FAULT_BMS") (class "Default")
      (node (ref "FAULT_IN") (pin "3") (pinfunction "3_3") (pintype "bidirectional"))
      (node (ref "R37") (pin "1") (pinfunction "1_1") (pintype "passive"))
    )
    (net (code "40") (name "FAULT_BMS_F") (class "Default")
      (node (ref "C23") (pin "1") (pinfunction "1_1") (pintype "passive"))
      (node (ref "C6") (pin "1") (pinfunction "1_1") (pintype "passive"))
      (node (ref "Q3") (pin "1") (pinfunction "G_1") (pintype "passive"))
      (node (ref "R17") (pin "2") (pinfunction "2_2") (pintype "passive"))
      (node (ref "R38") (pin "2") (pinfunction "2_2") (pintype "passive"))
    )
    (net (code "41") (name "FAULT_BMS_STAT") (class "Default")
      (node (ref "C8") (pin "1") (pinfunction "1_1") (pintype "passive"))
      (node (ref "D9") (pin "C") (pinfunction "C_C") (pintype "passive"))
      (node (ref "FAULT_STAT") (pin "2") (pinfunction "2_2") (pintype "bidirectional"))
      (node (ref "Q2") (pin "1") (pinfunction "G_1") (pintype "passive"))
      (node (ref "R22") (pin "1") (pinfunction "1_1") (pintype "passive"))
      (node (ref "U$2") (pin "$P1") (pinfunction "$P1_$P1") (pintype "bidirectional"))
      (node (ref "U$2") (pin "$P4") (pinfunction "$P4_$P4") (pintype "passive"))
    )
    (net (code "42") (name "FAULT_BMS_STATUS_3_3") (class "Default")
      (node (ref "Q2") (pin "3") (pinfunction "D_3") (pintype "passive"))
      (node (ref "R13") (pin "1") (pinfunction "1_1") (pintype "passive"))
      (node (ref "U1") (pin "22") (pinfunction "PB11_22") (pintype "bidirectional"))
    )
    (net (code "43") (name "FAULT_BSPD") (class "Default")
      (node (ref "C7") (pin "1") (pinfunction "1_1") (pintype "passive"))
      (node (ref "Q12") (pin "3") (pinfunction "D_3") (pintype "passive"))
      (node (ref "Q14") (pin "3") (pinfunction "D_3") (pintype "passive"))
      (node (ref "Q5") (pin "1") (pinfunction "G_1") (pintype "passive"))
      (node (ref "R16") (pin "2") (pinfunction "2_2") (pintype "passive"))
      (node (ref "R5") (pin "1") (pinfunction "1_1") (pintype "passive"))
    )
    (net (code "44") (name "FAULT_BSPD_STAT") (class "Default")
      (node (ref "C2") (pin "1") (pinfunction "1_1") (pintype "passive"))
      (node (ref "D2") (pin "C") (pinfunction "C_C") (pintype "passive"))
      (node (ref "FAULT_STAT") (pin "1") (pinfunction "1_1") (pintype "bidirectional"))
      (node (ref "Q1") (pin "1") (pinfunction "G_1") (pintype "passive"))
      (node (ref "R15") (pin "1") (pinfunction "1_1") (pintype "passive"))
      (node (ref "U$1") (pin "$P1") (pinfunction "$P1_$P1") (pintype "bidirectional"))
      (node (ref "U$1") (pin "$P4") (pinfunction "$P4_$P4") (pintype "passive"))
    )
    (net (code "45") (name "FAULT_BSPD_STATUS_3_3") (class "Default")
      (node (ref "Q1") (pin "3") (pinfunction "D_3") (pintype "passive"))
      (node (ref "R12") (pin "1") (pinfunction "1_1") (pintype "passive"))
      (node (ref "U1") (pin "27") (pinfunction "PB14_27") (pintype "bidirectional"))
    )
    (net (code "46") (name "FAULT_IMD") (class "Default")
      (node (ref "FAULT_IN") (pin "2") (pinfunction "2_2") (pintype "bidirectional"))
      (node (ref "R41") (pin "1") (pinfunction "1_1") (pintype "passive"))
    )
    (net (code "47") (name "FAULT_IMD_F") (class "Default")
      (node (ref "C26") (pin "1") (pinfunction "1_1") (pintype "passive"))
      (node (ref "C5") (pin "1") (pinfunction "1_1") (pintype "passive"))
      (node (ref "Q16") (pin "1") (pinfunction "G_1") (pintype "passive"))
      (node (ref "R18") (pin "2") (pinfunction "2_2") (pintype "passive"))
      (node (ref "R42") (pin "2") (pinfunction "2_2") (pintype "passive"))
    )
    (net (code "48") (name "FAULT_IMD_STAT") (class "Default")
      (node (ref "C9") (pin "1") (pinfunction "1_1") (pintype "passive"))
      (node (ref "D15") (pin "C") (pinfunction "C_C") (pintype "passive"))
      (node (ref "FAULT_STAT") (pin "3") (pinfunction "3_3") (pintype "bidirectional"))
      (node (ref "Q9") (pin "1") (pinfunction "G_1") (pintype "passive"))
      (node (ref "R21") (pin "1") (pinfunction "1_1") (pintype "passive"))
      (node (ref "U$3") (pin "$P1") (pinfunction "$P1_$P1") (pintype "bidirectional"))
      (node (ref "U$3") (pin "$P4") (pinfunction "$P4_$P4") (pintype "passive"))
    )
    (net (code "49") (name "FAULT_IMD_STATUS_3_3") (class "Default")
      (node (ref "Q9") (pin "3") (pinfunction "D_3") (pintype "passive"))
      (node (ref "R14") (pin "1") (pinfunction "1_1") (pintype "passive"))
      (node (ref "U1") (pin "13") (pinfunction "PA3_13") (pintype "bidirectional"))
    )
    (net (code "50") (name "FAULT_RESET") (class "Default")
      (node (ref "FAULT_IN") (pin "1") (pinfunction "1_1") (pintype "bidirectional"))
      (node (ref "R33") (pin "1") (pinfunction "1_1") (pintype "passive"))
    )
    (net (code "51") (name "FAULT_RESET_F") (class "Default")
      (node (ref "C22") (pin "1") (pinfunction "1_1") (pintype "passive"))
      (node (ref "Q11") (pin "1") (pinfunction "G_1") (pintype "passive"))
      (node (ref "Q15") (pin "1") (pinfunction "G_1") (pintype "passive"))
      (node (ref "Q6") (pin "1") (pinfunction "G_1") (pintype "passive"))
      (node (ref "R25") (pin "1") (pinfunction "1_1") (pintype "passive"))
      (node (ref "R34") (pin "2") (pinfunction "2_2") (pintype "passive"))
    )
    (net (code "52") (name "GND") (class "Default")
      (node (ref "BRAKE") (pin "B") (pinfunction "B_B") (pintype "passive"))
      (node (ref "C1") (pin "2") (pinfunction "2_2") (pintype "passive"))
      (node (ref "C10") (pin "-") (pinfunction "-_-") (pintype "passive"))
      (node (ref "C11") (pin "2") (pinfunction "2_2") (pintype "passive"))
      (node (ref "C12") (pin "2") (pinfunction "2_2") (pintype "passive"))
      (node (ref "C13") (pin "2") (pinfunction "2_2") (pintype "passive"))
      (node (ref "C14") (pin "2") (pinfunction "2_2") (pintype "passive"))
      (node (ref "C15") (pin "2") (pinfunction "2_2") (pintype "passive"))
      (node (ref "C16") (pin "2") (pinfunction "2_2") (pintype "passive"))
      (node (ref "C17") (pin "2") (pinfunction "2_2") (pintype "passive"))
      (node (ref "C18") (pin "2") (pinfunction "2_2") (pintype "passive"))
      (node (ref "C19") (pin "2") (pinfunction "2_2") (pintype "passive"))
      (node (ref "C2") (pin "2") (pinfunction "2_2") (pintype "passive"))
      (node (ref "C20") (pin "2") (pinfunction "2_2") (pintype "passive"))
      (node (ref "C22") (pin "2") (pinfunction "2_2") (pintype "passive"))
      (node (ref "C23") (pin "2") (pinfunction "2_2") (pintype "passive"))
      (node (ref "C24") (pin "2") (pinfunction "2_2") (pintype "passive"))
      (node (ref "C25") (pin "2") (pinfunction "2_2") (pintype "passive"))
      (node (ref "C26") (pin "2") (pinfunction "2_2") (pintype "passive"))
      (node (ref "C27") (pin "2") (pinfunction "2_2") (pintype "passive"))
      (node (ref "C28") (pin "2") (pinfunction "2_2") (pintype "passive"))
      (node (ref "C29") (pin "2") (pinfunction "2_2") (pintype "passive"))
      (node (ref "C3") (pin "2") (pinfunction "2_2") (pintype "passive"))
      (node (ref "C30") (pin "2") (pinfunction "2_2") (pintype "passive"))
      (node (ref "C31") (pin "2") (pinfunction "2_2") (pintype "passive"))
      (node (ref "C32") (pin "2") (pinfunction "2_2") (pintype "passive"))
      (node (ref "C33") (pin "2") (pinfunction "2_2") (pintype "passive"))
      (node (ref "C34") (pin "2") (pinfunction "2_2") (pintype "passive"))
      (node (ref "C35") (pin "2") (pinfunction "2_2") (pintype "passive"))
      (node (ref "C36") (pin "2") (pinfunction "2_2") (pintype "passive"))
      (node (ref "C37") (pin "2") (pinfunction "2_2") (pintype "passive"))
      (node (ref "C38") (pin "2") (pinfunction "2_2") (pintype "passive"))
      (node (ref "C39") (pin "2") (pinfunction "2_2") (pintype "passive"))
      (node (ref "C4") (pin "2") (pinfunction "2_2") (pintype "passive"))
      (node (ref "C40") (pin "2") (pinfunction "2_2") (pintype "passive"))
      (node (ref "C41") (pin "2") (pinfunction "2_2") (pintype "passive"))
      (node (ref "C42") (pin "2") (pinfunction "2_2") (pintype "passive"))
      (node (ref "C43") (pin "2") (pinfunction "2_2") (pintype "passive"))
      (node (ref "C44") (pin "2") (pinfunction "2_2") (pintype "passive"))
      (node (ref "C45") (pin "2") (pinfunction "2_2") (pintype "passive"))
      (node (ref "C46") (pin "2") (pinfunction "2_2") (pintype "passive"))
      (node (ref "C5") (pin "2") (pinfunction "2_2") (pintype "passive"))
      (node (ref "C6") (pin "2") (pinfunction "2_2") (pintype "passive"))
      (node (ref "C7") (pin "2") (pinfunction "2_2") (pintype "passive"))
      (node (ref "C8") (pin "2") (pinfunction "2_2") (pintype "passive"))
      (node (ref "C9") (pin "2") (pinfunction "2_2") (pintype "passive"))
      (node (ref "CURR") (pin "B") (pinfunction "B_B") (pintype "passive"))
      (node (ref "CURRENT_SENSE_SUPPLY") (pin "2") (pinfunction "2_2") (pintype "bidirectional"))
      (node (ref "D1") (pin "C") (pinfunction "C_C") (pintype "passive"))
      (node (ref "D4") (pin "C") (pinfunction "C_C") (pintype "passive"))
      (node (ref "D7") (pin "C") (pinfunction "C_C") (pintype "passive"))
      (node (ref "D8") (pin "3") (pinfunction "3_3") (pintype "passive"))
      (node (ref "H1") (pin "B3,0") (pinfunction "MOUNT_B3,0") (pintype "passive"))
      (node (ref "H2") (pin "B3,0") (pinfunction "MOUNT_B3,0") (pintype "passive"))
      (node (ref "H3") (pin "B3,0") (pinfunction "MOUNT_B3,0") (pintype "passive"))
      (node (ref "H4") (pin "B3,0") (pinfunction "MOUNT_B3,0") (pintype "passive"))
      (node (ref "JP1") (pin "5") (pinfunction "5_5") (pintype "passive"))
      (node (ref "JP2") (pin "5") (pinfunction "5_5") (pintype "passive"))
      (node (ref "POWER") (pin "2") (pinfunction "2_2") (pintype "bidirectional"))
      (node (ref "Q1") (pin "2") (pinfunction "S_2") (pintype "passive"))
      (node (ref "Q10") (pin "2") (pinfunction "S_2") (pintype "passive"))
      (node (ref "Q12") (pin "2") (pinfunction "S_2") (pintype "passive"))
      (node (ref "Q13") (pin "2") (pinfunction "S_2") (pintype "passive"))
      (node (ref "Q14") (pin "2") (pinfunction "S_2") (pintype "passive"))
      (node (ref "Q16") (pin "2") (pinfunction "S_2") (pintype "passive"))
      (node (ref "Q2") (pin "2") (pinfunction "S_2") (pintype "passive"))
      (node (ref "Q3") (pin "2") (pinfunction "S_2") (pintype "passive"))
      (node (ref "Q4") (pin "2") (pinfunction "S_2") (pintype "passive"))
      (node (ref "Q5") (pin "2") (pinfunction "S_2") (pintype "passive"))
      (node (ref "Q7") (pin "2") (pinfunction "S_2") (pintype "passive"))
      (node (ref "Q8") (pin "2") (pinfunction "S_2") (pintype "passive"))
      (node (ref "Q9") (pin "2") (pinfunction "S_2") (pintype "passive"))
      (node (ref "R16") (pin "1") (pinfunction "1_1") (pintype "passive"))
      (node (ref "R17") (pin "1") (pinfunction "1_1") (pintype "passive"))
      (node (ref "R18") (pin "1") (pinfunction "1_1") (pintype "passive"))
      (node (ref "R2") (pin "1") (pinfunction "1_1") (pintype "passive"))
      (node (ref "R3") (pin "1") (pinfunction "1_1") (pintype "passive"))
      (node (ref "R30") (pin "1") (pinfunction "1_1") (pintype "passive"))
      (node (ref "R31") (pin "1") (pinfunction "1_1") (pintype "passive"))
      (node (ref "R32") (pin "1") (pinfunction "1_1") (pintype "passive"))
      (node (ref "R4") (pin "1") (pinfunction "1_1") (pintype "passive"))
      (node (ref "R40") (pin "1") (pinfunction "1_1") (pintype "passive"))
      (node (ref "R43") (pin "1") (pinfunction "1_1") (pintype "passive"))
      (node (ref "R71") (pin "1") (pinfunction "1_1") (pintype "passive"))
      (node (ref "R72") (pin "1") (pinfunction "1_1") (pintype "passive"))
      (node (ref "R73") (pin "1") (pinfunction "1_1") (pintype "passive"))
      (node (ref "R76") (pin "1") (pinfunction "1_1") (pintype "passive"))
      (node (ref "R81") (pin "1") (pinfunction "1_1") (pintype "passive"))
      (node (ref "R83") (pin "1") (pinfunction "1_1") (pintype "passive"))
      (node (ref "U$10") (pin "1") (pinfunction "GND_1") (pintype "bidirectional"))
      (node (ref "U$11") (pin "2") (pinfunction "VSS_2") (pintype "bidirectional"))
      (node (ref "U$13") (pin "2") (pinfunction "GND_2") (pintype "bidirectional"))
      (node (ref "U$14") (pin "A") (pinfunction "A_A") (pintype "passive"))
      (node (ref "U$15") (pin "2") (pinfunction "GND_2") (pintype "bidirectional"))
      (node (ref "U$16") (pin "2") (pinfunction "GND_2") (pintype "bidirectional"))
      (node (ref "U$17") (pin "2") (pinfunction "GND_2") (pintype "bidirectional"))
      (node (ref "U$19") (pin "A") (pinfunction "A_A") (pintype "passive"))
      (node (ref "U$20") (pin "2") (pinfunction "GND_2") (pintype "bidirectional"))
      (node (ref "U$21") (pin "A") (pinfunction "A_A") (pintype "passive"))
      (node (ref "U$22") (pin "2") (pinfunction "GND_2") (pintype "bidirectional"))
      (node (ref "U$23") (pin "2") (pinfunction "GND_2") (pintype "bidirectional"))
      (node (ref "U$24") (pin "2") (pinfunction "GND_2") (pintype "bidirectional"))
      (node (ref "U$25") (pin "A") (pinfunction "A_A") (pintype "passive"))
      (node (ref "U$26") (pin "A") (pinfunction "A_A") (pintype "passive"))
      (node (ref "U$27") (pin "3") (pinfunction "GND_3") (pintype "output"))
      (node (ref "U$28") (pin "P7") (pinfunction "GND_P7") (pintype "bidirectional"))
      (node (ref "U$29") (pin "A") (pinfunction "A_A") (pintype "passive"))
      (node (ref "U$30") (pin "2") (pinfunction "GND_2") (pintype "bidirectional"))
      (node (ref "U$31") (pin "2") (pinfunction "GND_2") (pintype "bidirectional"))
      (node (ref "U$32") (pin "A") (pinfunction "A_A") (pintype "passive"))
      (node (ref "U$33") (pin "A") (pinfunction "A_A") (pintype "passive"))
      (node (ref "U$34") (pin "A") (pinfunction "A_A") (pintype "passive"))
      (node (ref "U$36") (pin "A") (pinfunction "A_A") (pintype "passive"))
      (node (ref "U$37") (pin "A") (pinfunction "A_A") (pintype "passive"))
      (node (ref "U$38") (pin "A") (pinfunction "A_A") (pintype "passive"))
      (node (ref "U$39") (pin "A") (pinfunction "A_A") (pintype "passive"))
      (node (ref "U$4") (pin "2") (pinfunction "E_2") (pintype "passive"))
      (node (ref "U$5") (pin "2") (pinfunction "GND_2") (pintype "bidirectional"))
      (node (ref "U$7") (pin "3") (pinfunction "GND_3") (pintype "bidirectional"))
      (node (ref "U$8") (pin "2") (pinfunction "2_2") (pintype "passive"))
      (node (ref "U$9") (pin "1") (pinfunction "GND_1") (pintype "bidirectional"))
      (node (ref "U1") (pin "20") (pinfunction "PB2_20") (pintype "bidirectional"))
      (node (ref "U1") (pin "23") (pinfunction "VSS_1_23") (pintype "bidirectional"))
      (node (ref "U1") (pin "35") (pinfunction "VSS_2_35") (pintype "passive"))
      (node (ref "U1") (pin "44") (pinfunction "BOOT0_44") (pintype "bidirectional"))
      (node (ref "U1") (pin "47") (pinfunction "VSS_3_47") (pintype "passive"))
      (node (ref "U1") (pin "8") (pinfunction "VSSA_8") (pintype "passive"))
      (node (ref "U2") (pin "20") (pinfunction "PB2_20") (pintype "bidirectional"))
      (node (ref "U2") (pin "23") (pinfunction "VSS_1_23") (pintype "bidirectional"))
      (node (ref "U2") (pin "35") (pinfunction "VSS_2_35") (pintype "passive"))
      (node (ref "U2") (pin "44") (pinfunction "BOOT0_44") (pintype "bidirectional"))
      (node (ref "U2") (pin "47") (pinfunction "VSS_3_47") (pintype "passive"))
      (node (ref "U2") (pin "8") (pinfunction "VSSA_8") (pintype "passive"))
    )
    (net (code "53") (name "HALL_FL") (class "Default")
      (node (ref "HALL_SENSOR_INPUT") (pin "1") (pinfunction "1_1") (pintype "bidirectional"))
      (node (ref "R57") (pin "1") (pinfunction "1_1") (pintype "passive"))
    )
    (net (code "54") (name "HALL_FL_F") (class "Default")
      (node (ref "C33") (pin "1") (pinfunction "1_1") (pintype "passive"))
      (node (ref "R58") (pin "2") (pinfunction "2_2") (pintype "passive"))
      (node (ref "U2") (pin "11") (pinfunction "PA1_11") (pintype "bidirectional"))
    )
    (net (code "55") (name "HALL_FR") (class "Default")
      (node (ref "HALL_SENSOR_INPUT") (pin "2") (pinfunction "2_2") (pintype "bidirectional"))
      (node (ref "R59") (pin "1") (pinfunction "1_1") (pintype "passive"))
    )
    (net (code "56") (name "HALL_FR_F") (class "Default")
      (node (ref "C34") (pin "1") (pinfunction "1_1") (pintype "passive"))
      (node (ref "R60") (pin "2") (pinfunction "2_2") (pintype "passive"))
      (node (ref "U2") (pin "10") (pinfunction "PA0-WKUP_10") (pintype "bidirectional"))
    )
    (net (code "57") (name "HALL_RL") (class "Default")
      (node (ref "HALL_SENSOR_INPUT") (pin "3") (pinfunction "3_3") (pintype "bidirectional"))
      (node (ref "R61") (pin "1") (pinfunction "1_1") (pintype "passive"))
    )
    (net (code "58") (name "HALL_RL_F") (class "Default")
      (node (ref "C35") (pin "1") (pinfunction "1_1") (pintype "passive"))
      (node (ref "R62") (pin "2") (pinfunction "2_2") (pintype "passive"))
      (node (ref "U2") (pin "12") (pinfunction "PA2_12") (pintype "bidirectional"))
    )
    (net (code "59") (name "HALL_RR") (class "Default")
      (node (ref "HALL_SENSOR_INPUT") (pin "4") (pinfunction "4_4") (pintype "bidirectional"))
      (node (ref "R63") (pin "1") (pinfunction "1_1") (pintype "passive"))
    )
    (net (code "60") (name "HALL_RR_F") (class "Default")
      (node (ref "C36") (pin "1") (pinfunction "1_1") (pintype "passive"))
      (node (ref "R64") (pin "2") (pinfunction "2_2") (pintype "passive"))
      (node (ref "U2") (pin "13") (pinfunction "PA3_13") (pintype "bidirectional"))
    )
    (net (code "61") (name "HV_CONNECTED_3_3") (class "Default")
      (node (ref "Q10") (pin "3") (pinfunction "D_3") (pintype "passive"))
      (node (ref "Q8") (pin "1") (pinfunction "G_1") (pintype "passive"))
      (node (ref "R23") (pin "1") (pinfunction "1_1") (pintype "passive"))
      (node (ref "U$7") (pin "2") (pinfunction "A_2") (pintype "input"))
      (node (ref "U1") (pin "21") (pinfunction "PB10_21") (pintype "bidirectional"))
    )
    (net (code "62") (name "Net-(C17-Pad1)") (class "Default")
      (node (ref "C17") (pin "1") (pinfunction "1_1") (pintype "passive"))
      (node (ref "R19") (pin "1") (pinfunction "1_1") (pintype "passive"))
    )
    (net (code "63") (name "Net-(C18-Pad1)") (class "Default")
      (node (ref "C18") (pin "1") (pinfunction "1_1") (pintype "passive"))
      (node (ref "R20") (pin "1") (pinfunction "1_1") (pintype "passive"))
    )
    (net (code "64") (name "Net-(D1-PadA)") (class "Default")
      (node (ref "D1") (pin "A") (pinfunction "A_A") (pintype "passive"))
      (node (ref "R21") (pin "2") (pinfunction "2_2") (pintype "passive"))
    )
    (net (code "65") (name "Net-(D4-PadA)") (class "Default")
      (node (ref "D4") (pin "A") (pinfunction "A_A") (pintype "passive"))
      (node (ref "R22") (pin "2") (pinfunction "2_2") (pintype "passive"))
    )
    (net (code "66") (name "Net-(D7-PadA)") (class "Default")
      (node (ref "D7") (pin "A") (pinfunction "A_A") (pintype "passive"))
      (node (ref "R15") (pin "2") (pinfunction "2_2") (pintype "passive"))
    )
    (net (code "67") (name "Net-(D10-PadA)") (class "Default")
      (node (ref "D10") (pin "A") (pinfunction "A_A") (pintype "passive"))
      (node (ref "R27") (pin "2") (pinfunction "2_2") (pintype "passive"))
    )
    (net (code "68") (name "Net-(D11-PadC)") (class "Default")
      (node (ref "D11") (pin "C") (pinfunction "C_C") (pintype "passive"))
      (node (ref "R2") (pin "2") (pinfunction "2_2") (pintype "passive"))
    )
    (net (code "69") (name "Net-(D12-PadC)") (class "Default")
      (node (ref "D12") (pin "C") (pinfunction "C_C") (pintype "passive"))
      (node (ref "R4") (pin "2") (pinfunction "2_2") (pintype "passive"))
    )
    (net (code "70") (name "Net-(D13-PadA)") (class "Default")
      (node (ref "D13") (pin "A") (pinfunction "A_A") (pintype "passive"))
      (node (ref "R29") (pin "2") (pinfunction "2_2") (pintype "passive"))
    )
    (net (code "71") (name "Net-(L4-1)") (class "Default")
      (node (ref "FUSE") (pin "P$2") (pinfunction "2_P$2") (pintype "passive"))
      (node (ref "FUSE") (pin "P$3") (pinfunction "2_P$3") (pintype "passive"))
      (node (ref "L4") (pin "P$1") (pinfunction "1_P$1") (pintype "passive"))
    )
    (net (code "72") (name "Net-(Q3-D)") (class "Default")
      (node (ref "D9") (pin "A") (pinfunction "A_A") (pintype "passive"))
      (node (ref "Q3") (pin "3") (pinfunction "D_3") (pintype "passive"))
      (node (ref "U$2") (pin "$P12") (pinfunction "$P12_$P12") (pintype "bidirectional"))
    )
    (net (code "73") (name "Net-(Q4-D)") (class "Default")
      (node (ref "Q4") (pin "3") (pinfunction "D_3") (pintype "passive"))
      (node (ref "U$6") (pin "NEG") (pinfunction "B_NEG") (pintype "output"))
    )
    (net (code "74") (name "Net-(Q5-D)") (class "Default")
      (node (ref "D2") (pin "A") (pinfunction "A_A") (pintype "passive"))
      (node (ref "Q5") (pin "3") (pinfunction "D_3") (pintype "passive"))
      (node (ref "U$1") (pin "$P12") (pinfunction "$P12_$P12") (pintype "bidirectional"))
    )
    (net (code "75") (name "Net-(Q6-D)") (class "Default")
      (node (ref "Q6") (pin "3") (pinfunction "D_3") (pintype "passive"))
      (node (ref "U$1") (pin "$P3") (pinfunction "$P3_$P3") (pintype "passive"))
    )
    (net (code "76") (name "Net-(Q11-D)") (class "Default")
      (node (ref "Q11") (pin "3") (pinfunction "D_3") (pintype "passive"))
      (node (ref "U$2") (pin "$P3") (pinfunction "$P3_$P3") (pintype "passive"))
    )
    (net (code "77") (name "Net-(Q13-G)") (class "Default")
      (node (ref "Q13") (pin "1") (pinfunction "G_1") (pintype "passive"))
      (node (ref "R3") (pin "2") (pinfunction "2_2") (pintype "passive"))
      (node (ref "U$7") (pin "4") (pinfunction "Y_4") (pintype "input"))
    )
    (net (code "78") (name "Net-(Q15-D)") (class "Default")
      (node (ref "Q15") (pin "3") (pinfunction "D_3") (pintype "passive"))
      (node (ref "U$3") (pin "$P3") (pinfunction "$P3_$P3") (pintype "passive"))
    )
    (net (code "79") (name "Net-(Q16-D)") (class "Default")
      (node (ref "D15") (pin "A") (pinfunction "A_A") (pintype "passive"))
      (node (ref "Q16") (pin "3") (pinfunction "D_3") (pintype "passive"))
      (node (ref "U$3") (pin "$P12") (pinfunction "$P12_$P12") (pintype "bidirectional"))
    )
    (net (code "80") (name "Net-(Q18-D)") (class "Default")
      (node (ref "Q18") (pin "3") (pinfunction "D_3") (pintype "passive"))
      (node (ref "Q20") (pin "2") (pinfunction "S_2") (pintype "passive"))
    )
    (net (code "81") (name "Net-(Q18-S)") (class "Default")
      (node (ref "Q18") (pin "2") (pinfunction "S_2") (pintype "passive"))
      (node (ref "Q21") (pin "3") (pinfunction "D_3") (pintype "passive"))
    )
    (net (code "82") (name "Net-(R10-Pad2)") (class "Default")
      (node (ref "R10") (pin "2") (pinfunction "2_2") (pintype "passive"))
      (node (ref "R45") (pin "1") (pinfunction "1_1") (pintype "passive"))
      (node (ref "R77") (pin "1") (pinfunction "1_1") (pintype "passive"))
      (node (ref "U$14") (pin "C") (pinfunction "C_C") (pintype "passive"))
    )
    (net (code "83") (name "Net-(R33-Pad2)") (class "Default")
      (node (ref "R33") (pin "2") (pinfunction "2_2") (pintype "passive"))
      (node (ref "R34") (pin "1") (pinfunction "1_1") (pintype "passive"))
      (node (ref "U$25") (pin "C") (pinfunction "C_C") (pintype "passive"))
    )
    (net (code "84") (name "Net-(R35-Pad1)") (class "Default")
      (node (ref "R35") (pin "1") (pinfunction "1_1") (pintype "passive"))
      (node (ref "R53") (pin "2") (pinfunction "2_2") (pintype "passive"))
      (node (ref "R54") (pin "1") (pinfunction "1_1") (pintype "passive"))
      (node (ref "U$34") (pin "C") (pinfunction "C_C") (pintype "passive"))
    )
    (net (code "85") (name "Net-(R37-Pad2)") (class "Default")
      (node (ref "R37") (pin "2") (pinfunction "2_2") (pintype "passive"))
      (node (ref "R38") (pin "1") (pinfunction "1_1") (pintype "passive"))
      (node (ref "U$26") (pin "C") (pinfunction "C_C") (pintype "passive"))
    )
    (net (code "86") (name "Net-(R41-Pad2)") (class "Default")
      (node (ref "R41") (pin "2") (pinfunction "2_2") (pintype "passive"))
      (node (ref "R42") (pin "1") (pinfunction "1_1") (pintype "passive"))
      (node (ref "U$29") (pin "C") (pinfunction "C_C") (pintype "passive"))
    )
    (net (code "87") (name "Net-(R49-Pad2)") (class "Default")
      (node (ref "R49") (pin "2") (pinfunction "2_2") (pintype "passive"))
      (node (ref "R50") (pin "1") (pinfunction "1_1") (pintype "passive"))
      (node (ref "U$32") (pin "C") (pinfunction "C_C") (pintype "passive"))
    )
    (net (code "88") (name "Net-(R51-Pad2)") (class "Default")
      (node (ref "R51") (pin "2") (pinfunction "2_2") (pintype "passive"))
      (node (ref "R52") (pin "1") (pinfunction "1_1") (pintype "passive"))
      (node (ref "U$33") (pin "C") (pinfunction "C_C") (pintype "passive"))
    )
    (net (code "89") (name "Net-(R55-Pad2)") (class "Default")
      (node (ref "R55") (pin "2") (pinfunction "2_2") (pintype "passive"))
      (node (ref "R56") (pin "1") (pinfunction "1_1") (pintype "passive"))
      (node (ref "U$21") (pin "C") (pinfunction "C_C") (pintype "passive"))
    )
    (net (code "90") (name "Net-(R57-Pad2)") (class "Default")
      (node (ref "R57") (pin "2") (pinfunction "2_2") (pintype "passive"))
      (node (ref "R58") (pin "1") (pinfunction "1_1") (pintype "passive"))
      (node (ref "R65") (pin "1") (pinfunction "1_1") (pintype "passive"))
      (node (ref "U$36") (pin "C") (pinfunction "C_C") (pintype "passive"))
    )
    (net (code "91") (name "Net-(R59-Pad2)") (class "Default")
      (node (ref "R59") (pin "2") (pinfunction "2_2") (pintype "passive"))
      (node (ref "R60") (pin "1") (pinfunction "1_1") (pintype "passive"))
      (node (ref "R66") (pin "1") (pinfunction "1_1") (pintype "passive"))
      (node (ref "U$37") (pin "C") (pinfunction "C_C") (pintype "passive"))
    )
    (net (code "92") (name "Net-(R61-Pad2)") (class "Default")
      (node (ref "R61") (pin "2") (pinfunction "2_2") (pintype "passive"))
      (node (ref "R62") (pin "1") (pinfunction "1_1") (pintype "passive"))
      (node (ref "R67") (pin "1") (pinfunction "1_1") (pintype "passive"))
      (node (ref "U$38") (pin "C") (pinfunction "C_C") (pintype "passive"))
    )
    (net (code "93") (name "Net-(R63-Pad2)") (class "Default")
      (node (ref "R63") (pin "2") (pinfunction "2_2") (pintype "passive"))
      (node (ref "R64") (pin "1") (pinfunction "1_1") (pintype "passive"))
      (node (ref "R68") (pin "1") (pinfunction "1_1") (pintype "passive"))
      (node (ref "U$39") (pin "C") (pinfunction "C_C") (pintype "passive"))
    )
    (net (code "94") (name "Net-(R78-Pad2)") (class "Default")
      (node (ref "R78") (pin "2") (pinfunction "2_2") (pintype "passive"))
      (node (ref "R79") (pin "1") (pinfunction "1_1") (pintype "passive"))
      (node (ref "R82") (pin "1") (pinfunction "1_1") (pintype "passive"))
      (node (ref "U$19") (pin "C") (pinfunction "C_C") (pintype "passive"))
    )
    (net (code "95") (name "Net-(U$1-Pad$P8)") (class "Default")
      (node (ref "U$1") (pin "$P8") (pinfunction "$P8_$P8") (pintype "passive"))
      (node (ref "U$2") (pin "$P9") (pinfunction "$P9_$P9") (pintype "passive"))
    )
    (net (code "96") (name "Net-(U$2-Pad$P8)") (class "Default")
      (node (ref "U$2") (pin "$P8") (pinfunction "$P8_$P8") (pintype "passive"))
      (node (ref "U$3") (pin "$P9") (pinfunction "$P9_$P9") (pintype "passive"))
    )
    (net (code "97") (name "Net-(U$4-B)") (class "Default")
      (node (ref "R9") (pin "2") (pinfunction "2_2") (pintype "passive"))
      (node (ref "U$4") (pin "1") (pinfunction "B_1") (pintype "passive"))
    )
    (net (code "98") (name "Net-(U$5-OUT)") (class "Default")
      (node (ref "R1") (pin "2") (pinfunction "2_2") (pintype "passive"))
      (node (ref "U$5") (pin "1") (pinfunction "OUT_1") (pintype "output"))
    )
    (net (code "99") (name "Net-(U$12-B)") (class "Default")
      (node (ref "R7") (pin "2") (pinfunction "2_2") (pintype "passive"))
      (node (ref "U$12") (pin "5") (pinfunction "B_5") (pintype "passive"))
      (node (ref "U$18") (pin "1") (pinfunction "+IN_1") (pintype "input"))
    )
    (net (code "100") (name "Net-(U$13-+IN)") (class "Default")
      (node (ref "C40") (pin "1") (pinfunction "1_1") (pintype "passive"))
      (node (ref "R45") (pin "2") (pinfunction "2_2") (pintype "passive"))
      (node (ref "U$13") (pin "1") (pinfunction "+IN_1") (pintype "input"))
    )
    (net (code "101") (name "Net-(U$15-+IN)") (class "Default")
      (node (ref "C41") (pin "1") (pinfunction "1_1") (pintype "passive"))
      (node (ref "R79") (pin "2") (pinfunction "2_2") (pintype "passive"))
      (node (ref "U$15") (pin "1") (pinfunction "+IN_1") (pintype "input"))
    )
    (net (code "102") (name "Net-(U$20-OUT)") (class "Default")
      (node (ref "R36") (pin "2") (pinfunction "2_2") (pintype "passive"))
      (node (ref "U$20") (pin "1") (pinfunction "OUT_1") (pintype "output"))
    )
    (net (code "103") (name "Net-(U$22-+IN)") (class "Default")
      (node (ref "C29") (pin "1") (pinfunction "1_1") (pintype "passive"))
      (node (ref "R50") (pin "2") (pinfunction "2_2") (pintype "passive"))
      (node (ref "U$22") (pin "1") (pinfunction "+IN_1") (pintype "input"))
    )
    (net (code "104") (name "Net-(U$23-+IN)") (class "Default")
      (node (ref "C30") (pin "1") (pinfunction "1_1") (pintype "passive"))
      (node (ref "R52") (pin "2") (pinfunction "2_2") (pintype "passive"))
      (node (ref "U$23") (pin "1") (pinfunction "+IN_1") (pintype "input"))
    )
    (net (code "105") (name "Net-(U$24-+IN)") (class "Default")
      (node (ref "C31") (pin "1") (pinfunction "1_1") (pintype "passive"))
      (node (ref "R54") (pin "2") (pinfunction "2_2") (pintype "passive"))
      (node (ref "U$24") (pin "1") (pinfunction "+IN_1") (pintype "input"))
    )
    (net (code "106") (name "OC_TH") (class "Default")
      (node (ref "R11") (pin "1") (pinfunction "1_1") (pintype "passive"))
      (node (ref "R43") (pin "2") (pinfunction "2_2") (pintype "passive"))
      (node (ref "U$17") (pin "4") (pinfunction "-IN_4") (pintype "input"))
      (node (ref "U$31") (pin "4") (pinfunction "-IN_4") (pintype "input"))
    )
    (net (code "107") (name "PA11") (class "Default")
      (node (ref "U2") (pin "32") (pinfunction "PA11_32") (pintype "power_in"))
    )
    (net (code "108") (name "PRECHARGE_COMPLETE") (class "Default")
      (node (ref "LIGHTING") (pin "5") (pinfunction "5_5") (pintype "bidirectional"))
      (node (ref "R55") (pin "1") (pinfunction "1_1") (pintype "passive"))
    )
    (net (code "109") (name "PRECHARGE_COMPLETE_3_3") (class "Default")
      (node (ref "Q7") (pin "3") (pinfunction "D_3") (pintype "passive"))
      (node (ref "R74") (pin "1") (pinfunction "1_1") (pintype "passive"))
      (node (ref "U1") (pin "42") (pinfunction "PB6_42") (pintype "bidirectional"))
    )
    (net (code "110") (name "PRECHARGE_COMP_F") (class "Default")
      (node (ref "C32") (pin "1") (pinfunction "1_1") (pintype "passive"))
      (node (ref "Q7") (pin "1") (pinfunction "G_1") (pintype "passive"))
      (node (ref "R56") (pin "2") (pinfunction "2_2") (pintype "passive"))
    )
    (net (code "111") (name "PWR") (class "Default")
      (node (ref "FUSE") (pin "P$1") (pinfunction "1_P$1") (pintype "passive"))
      (node (ref "FUSE") (pin "P$4") (pinfunction "1_P$4") (pintype "passive"))
      (node (ref "POWER") (pin "1") (pinfunction "1_1") (pintype "bidirectional"))
    )
    (net (code "112") (name "RTDS_EN") (class "Default")
      (node (ref "Q4") (pin "1") (pinfunction "G_1") (pintype "passive"))
      (node (ref "U1") (pin "39") (pinfunction "PB3_39") (pintype "bidirectional"))
    )
    (net (code "113") (name "RTD_EN") (class "Default")
      (node (ref "Q21") (pin "1") (pinfunction "G_1") (pintype "passive"))
      (node (ref "R32") (pin "2") (pinfunction "2_2") (pintype "passive"))
      (node (ref "U1") (pin "45") (pinfunction "PB8_45") (pintype "bidirectional"))
    )
    (net (code "114") (name "SCL_TC") (class "Default")
      (node (ref "R48") (pin "2") (pinfunction "2_2") (pintype "passive"))
      (node (ref "U$12") (pin "3") (pinfunction "SCL_3") (pintype "passive"))
      (node (ref "U2") (pin "42") (pinfunction "PB6_42") (pintype "bidirectional"))
    )
    (net (code "115") (name "SC_TH") (class "Default")
      (node (ref "R39") (pin "1") (pinfunction "1_1") (pintype "passive"))
      (node (ref "R40") (pin "2") (pinfunction "2_2") (pintype "passive"))
      (node (ref "U$16") (pin "3") (pinfunction "+IN_3") (pintype "input"))
      (node (ref "U$30") (pin "3") (pinfunction "+IN_3") (pintype "input"))
    )
    (net (code "116") (name "SDA_TC") (class "Default")
      (node (ref "R47") (pin "2") (pinfunction "2_2") (pintype "passive"))
      (node (ref "U$12") (pin "4") (pinfunction "SDA_4") (pintype "passive"))
      (node (ref "U2") (pin "43") (pinfunction "PB7_43") (pintype "bidirectional"))
    )
    (net (code "117") (name "SPI1_MISO") (class "Default")
      (node (ref "U1") (pin "16") (pinfunction "PA6_16") (pintype "bidirectional"))
      (node (ref "U2") (pin "17") (pinfunction "PA7_17") (pintype "bidirectional"))
    )
    (net (code "118") (name "SPI1_MOSI") (class "Default")
      (node (ref "U1") (pin "17") (pinfunction "PA7_17") (pintype "bidirectional"))
      (node (ref "U2") (pin "16") (pinfunction "PA6_16") (pintype "bidirectional"))
    )
    (net (code "119") (name "SPI1_NSS") (class "Default")
      (node (ref "U1") (pin "14") (pinfunction "PA4_14") (pintype "bidirectional"))
      (node (ref "U2") (pin "14") (pinfunction "PA4_14") (pintype "bidirectional"))
    )
    (net (code "120") (name "SPI1_SCK") (class "Default")
      (node (ref "U1") (pin "15") (pinfunction "PA5_15") (pintype "bidirectional"))
      (node (ref "U2") (pin "15") (pinfunction "PA5_15") (pintype "bidirectional"))
    )
    (net (code "121") (name "STEERING_POS") (class "Default")
      (node (ref "R78") (pin "1") (pinfunction "1_1") (pintype "passive"))
      (node (ref "THROTTLE_TC") (pin "3") (pinfunction "3_3") (pintype "bidirectional"))
    )
    (net (code "122") (name "STEERING_POS_F") (class "Default")
      (node (ref "R80") (pin "2") (pinfunction "2_2") (pintype "passive"))
      (node (ref "U$15") (pin "3") (pinfunction "-IN_3") (pintype "input"))
      (node (ref "U$15") (pin "4") (pinfunction "OUT_4") (pintype "output"))
    )
    (net (code "123") (name "STEERING_POS_F_3_3") (class "Default")
      (node (ref "R80") (pin "1") (pinfunction "1_1") (pintype "passive"))
      (node (ref "R81") (pin "2") (pinfunction "2_2") (pintype "passive"))
      (node (ref "U1") (pin "12") (pinfunction "PA2_12") (pintype "bidirectional"))
    )
    (net (code "124") (name "SWCLK") (class "Default")
      (node (ref "JP1") (pin "4") (pinfunction "4_4") (pintype "passive"))
      (node (ref "U1") (pin "37") (pinfunction "PA14_37") (pintype "bidirectional"))
    )
    (net (code "125") (name "SWCLK_TC") (class "Default")
      (node (ref "JP2") (pin "4") (pinfunction "4_4") (pintype "passive"))
      (node (ref "U2") (pin "37") (pinfunction "PA14_37") (pintype "bidirectional"))
    )
    (net (code "126") (name "SWDIO") (class "Default")
      (node (ref "JP1") (pin "3") (pinfunction "3_3") (pintype "passive"))
      (node (ref "U1") (pin "34") (pinfunction "PA13_34") (pintype "bidirectional"))
    )
    (net (code "127") (name "SWDIO_TC") (class "Default")
      (node (ref "JP2") (pin "3") (pinfunction "3_3") (pintype "passive"))
      (node (ref "U2") (pin "34") (pinfunction "PA13_34") (pintype "bidirectional"))
    )
    (net (code "128") (name "THROTTLE_A") (class "Default")
      (node (ref "R49") (pin "1") (pinfunction "1_1") (pintype "passive"))
      (node (ref "THROTTLE_TC") (pin "1") (pinfunction "1_1") (pintype "bidirectional"))
    )
    (net (code "129") (name "THROTTLE_A_F") (class "Default")
      (node (ref "R69") (pin "2") (pinfunction "2_2") (pintype "passive"))
      (node (ref "U$12") (pin "6") (pinfunction "W_6") (pintype "passive"))
      (node (ref "U$22") (pin "3") (pinfunction "-IN_3") (pintype "input"))
      (node (ref "U$22") (pin "4") (pinfunction "OUT_4") (pintype "output"))
    )
    (net (code "130") (name "THROTTLE_A_F_3_3") (class "Default")
      (node (ref "R69") (pin "1") (pinfunction "1_1") (pintype "passive"))
      (node (ref "R73") (pin "2") (pinfunction "2_2") (pintype "passive"))
      (node (ref "U1") (pin "18") (pinfunction "PB0_18") (pintype "bidirectional"))
    )
    (net (code "131") (name "THROTTLE_B") (class "Default")
      (node (ref "R51") (pin "1") (pinfunction "1_1") (pintype "passive"))
      (node (ref "THROTTLE_TC") (pin "2") (pinfunction "2_2") (pintype "bidirectional"))
    )
    (net (code "132") (name "THROTTLE_B_F") (class "Default")
      (node (ref "R46") (pin "2") (pinfunction "2_2") (pintype "passive"))
      (node (ref "U$23") (pin "3") (pinfunction "-IN_3") (pintype "input"))
      (node (ref "U$23") (pin "4") (pinfunction "OUT_4") (pintype "output"))
    )
    (net (code "133") (name "THROTTLE_B_F_3_3") (class "Default")
      (node (ref "R46") (pin "1") (pinfunction "1_1") (pintype "passive"))
      (node (ref "R72") (pin "2") (pinfunction "2_2") (pintype "passive"))
      (node (ref "U1") (pin "19") (pinfunction "PB1_19") (pintype "bidirectional"))
    )
    (net (code "134") (name "THROTTLE_OUT") (class "Default")
      (node (ref "THROTTLE_TC") (pin "5") (pinfunction "5_5") (pintype "bidirectional"))
      (node (ref "U$18") (pin "3") (pinfunction "-IN_3") (pintype "input"))
      (node (ref "U$18") (pin "4") (pinfunction "OUT_4") (pintype "output"))
    )
    (net (code "135") (name "TSAL_EN") (class "Default")
      (node (ref "LIGHTING") (pin "1") (pinfunction "1_1") (pintype "bidirectional"))
      (node (ref "Q10") (pin "1") (pinfunction "G_1") (pintype "passive"))
    )
    (net (code "136") (name "TSAL_HV-") (class "Default")
      (node (ref "LIGHTING") (pin "3") (pinfunction "3_3") (pintype "bidirectional"))
      (node (ref "Q8") (pin "3") (pinfunction "D_3") (pintype "passive"))
    )
    (net (code "137") (name "TSAL_LV-") (class "Default")
      (node (ref "LIGHTING") (pin "2") (pinfunction "2_2") (pintype "bidirectional"))
      (node (ref "Q13") (pin "3") (pinfunction "D_3") (pintype "passive"))
    )
    (net (code "138") (name "unconnected-(U$1-Pad$P10)") (class "Default")
      (node (ref "U$1") (pin "$P10") (pinfunction "$P10_$P10") (pintype "passive"))
    )
    (net (code "139") (name "unconnected-(U$2-Pad$P10)") (class "Default")
      (node (ref "U$2") (pin "$P10") (pinfunction "$P10_$P10") (pintype "passive"))
    )
    (net (code "140") (name "unconnected-(U$3-Pad$P10)") (class "Default")
      (node (ref "U$3") (pin "$P10") (pinfunction "$P10_$P10") (pintype "passive"))
    )
    (net (code "141") (name "unconnected-(U$28-A1-PadP9)") (class "Default")
      (node (ref "U$28") (pin "P9") (pinfunction "A1_P9") (pintype "bidirectional"))
    )
    (net (code "142") (name "unconnected-(U$28-B1-PadP10)") (class "Default")
      (node (ref "U$28") (pin "P10") (pinfunction "B1_P10") (pintype "bidirectional"))
    )
    (net (code "143") (name "unconnected-(U$28-C1-PadP11)") (class "Default")
      (node (ref "U$28") (pin "P11") (pinfunction "C1_P11") (pintype "bidirectional"))
    )
    (net (code "144") (name "unconnected-(U$28-D1-PadP12)") (class "Default")
      (node (ref "U$28") (pin "P12") (pinfunction "D1_P12") (pintype "bidirectional"))
    )
    (net (code "145") (name "unconnected-(U$28-Y1-PadP13)") (class "Default")
      (node (ref "U$28") (pin "P13") (pinfunction "Y1_P13") (pintype "bidirectional"))
    )
    (net (code "146") (name "unconnected-(U1-PA8-Pad29)") (class "Default")
      (node (ref "U1") (pin "29") (pinfunction "PA8_29") (pintype "bidirectional"))
    )
    (net (code "147") (name "unconnected-(U1-PA9-Pad30)") (class "Default")
      (node (ref "U1") (pin "30") (pinfunction "PA9_30") (pintype "bidirectional"))
    )
    (net (code "148") (name "unconnected-(U1-PA15-Pad38)") (class "Default")
      (node (ref "U1") (pin "38") (pinfunction "PA15_38") (pintype "bidirectional"))
    )
    (net (code "149") (name "unconnected-(U1-PB7-Pad43)") (class "Default")
      (node (ref "U1") (pin "43") (pinfunction "PB7_43") (pintype "bidirectional"))
    )
    (net (code "150") (name "unconnected-(U1-PB9-Pad46)") (class "Default")
      (node (ref "U1") (pin "46") (pinfunction "PB9_46") (pintype "bidirectional"))
    )
    (net (code "151") (name "unconnected-(U1-PB12-Pad25)") (class "Default")
      (node (ref "U1") (pin "25") (pinfunction "PB12_25") (pintype "bidirectional"))
    )
    (net (code "152") (name "unconnected-(U1-PB15-Pad28)") (class "Default")
      (node (ref "U1") (pin "28") (pinfunction "PB15_28") (pintype "bidirectional"))
    )
    (net (code "153") (name "unconnected-(U1-PC14-OSC32_IN-Pad3)") (class "Default")
      (node (ref "U1") (pin "3") (pinfunction "PC14-OSC32_IN_3") (pintype "bidirectional"))
    )
    (net (code "154") (name "unconnected-(U1-PC15-OSC32_OUT-Pad4)") (class "Default")
      (node (ref "U1") (pin "4") (pinfunction "PC15-OSC32_OUT_4") (pintype "bidirectional"))
    )
    (net (code "155") (name "unconnected-(U1-PD0-OSC_IN-Pad5)") (class "Default")
      (node (ref "U1") (pin "5") (pinfunction "PD0-OSC_IN_5") (pintype "bidirectional"))
    )
    (net (code "156") (name "unconnected-(U1-PD1-OSC_OUT-Pad6)") (class "Default")
      (node (ref "U1") (pin "6") (pinfunction "PD1-OSC_OUT_6") (pintype "bidirectional"))
    )
    (net (code "157") (name "unconnected-(U1-VBAT-Pad1)") (class "Default")
      (node (ref "U1") (pin "1") (pinfunction "VBAT_1") (pintype "input"))
    )
    (net (code "158") (name "unconnected-(U2-PA8-Pad29)") (class "Default")
      (node (ref "U2") (pin "29") (pinfunction "PA8_29") (pintype "bidirectional"))
    )
    (net (code "159") (name "unconnected-(U2-PA9-Pad30)") (class "Default")
      (node (ref "U2") (pin "30") (pinfunction "PA9_30") (pintype "bidirectional"))
    )
    (net (code "160") (name "unconnected-(U2-PA10-Pad31)") (class "Default")
      (node (ref "U2") (pin "31") (pinfunction "PA10_31") (pintype "bidirectional"))
    )
    (net (code "161") (name "unconnected-(U2-PA12-Pad33)") (class "Default")
      (node (ref "U2") (pin "33") (pinfunction "PA12_33") (pintype "bidirectional"))
    )
    (net (code "162") (name "unconnected-(U2-PA15-Pad38)") (class "Default")
      (node (ref "U2") (pin "38") (pinfunction "PA15_38") (pintype "bidirectional"))
    )
    (net (code "163") (name "unconnected-(U2-PB0-Pad18)") (class "Default")
      (node (ref "U2") (pin "18") (pinfunction "PB0_18") (pintype "bidirectional"))
    )
    (net (code "164") (name "unconnected-(U2-PB1-Pad19)") (class "Default")
      (node (ref "U2") (pin "19") (pinfunction "PB1_19") (pintype "bidirectional"))
    )
    (net (code "165") (name "unconnected-(U2-PB3-Pad39)") (class "Default")
      (node (ref "U2") (pin "39") (pinfunction "PB3_39") (pintype "bidirectional"))
    )
    (net (code "166") (name "unconnected-(U2-PB4-Pad40)") (class "Default")
      (node (ref "U2") (pin "40") (pinfunction "PB4_40") (pintype "bidirectional"))
    )
    (net (code "167") (name "unconnected-(U2-PB5-Pad41)") (class "Default")
      (node (ref "U2") (pin "41") (pinfunction "PB5_41") (pintype "bidirectional"))
    )
    (net (code "168") (name "unconnected-(U2-PB8-Pad45)") (class "Default")
      (node (ref "U2") (pin "45") (pinfunction "PB8_45") (pintype "bidirectional"))
    )
    (net (code "169") (name "unconnected-(U2-PB9-Pad46)") (class "Default")
      (node (ref "U2") (pin "46") (pinfunction "PB9_46") (pintype "bidirectional"))
    )
    (net (code "170") (name "unconnected-(U2-PB10-Pad21)") (class "Default")
      (node (ref "U2") (pin "21") (pinfunction "PB10_21") (pintype "bidirectional"))
    )
    (net (code "171") (name "unconnected-(U2-PB11-Pad22)") (class "Default")
      (node (ref "U2") (pin "22") (pinfunction "PB11_22") (pintype "bidirectional"))
    )
    (net (code "172") (name "unconnected-(U2-PB12-Pad25)") (class "Default")
      (node (ref "U2") (pin "25") (pinfunction "PB12_25") (pintype "bidirectional"))
    )
    (net (code "173") (name "unconnected-(U2-PB13-Pad26)") (class "Default")
      (node (ref "U2") (pin "26") (pinfunction "PB13_26") (pintype "bidirectional"))
    )
    (net (code "174") (name "unconnected-(U2-PB14-Pad27)") (class "Default")
      (node (ref "U2") (pin "27") (pinfunction "PB14_27") (pintype "bidirectional"))
    )
    (net (code "175") (name "unconnected-(U2-PB15-Pad28)") (class "Default")
      (node (ref "U2") (pin "28") (pinfunction "PB15_28") (pintype "bidirectional"))
    )
    (net (code "176") (name "unconnected-(U2-PC14-OSC32_IN-Pad3)") (class "Default")
      (node (ref "U2") (pin "3") (pinfunction "PC14-OSC32_IN_3") (pintype "bidirectional"))
    )
    (net (code "177") (name "unconnected-(U2-PC15-OSC32_OUT-Pad4)") (class "Default")
      (node (ref "U2") (pin "4") (pinfunction "PC15-OSC32_OUT_4") (pintype "bidirectional"))
    )
    (net (code "178") (name "unconnected-(U2-PD0-OSC_IN-Pad5)") (class "Default")
      (node (ref "U2") (pin "5") (pinfunction "PD0-OSC_IN_5") (pintype "bidirectional"))
    )
    (net (code "179") (name "unconnected-(U2-PD1-OSC_OUT-Pad6)") (class "Default")
      (node (ref "U2") (pin "6") (pinfunction "PD1-OSC_OUT_6") (pintype "bidirectional"))
    )
    (net (code "180") (name "unconnected-(U2-VBAT-Pad1)") (class "Default")
      (node (ref "U2") (pin "1") (pinfunction "VBAT_1") (pintype "input"))
    )
    (net (code "181") (name "~{RST_TC}") (class "Default")
      (node (ref "JP2") (pin "2") (pinfunction "2_2") (pintype "passive"))
      (node (ref "R28") (pin "2") (pinfunction "2_2") (pintype "passive"))
      (node (ref "U2") (pin "7") (pinfunction "NRST_7") (pintype "bidirectional"))
    )
    (net (code "182") (name "~{RST}") (class "Default")
      (node (ref "JP1") (pin "2") (pinfunction "2_2") (pintype "passive"))
      (node (ref "R26") (pin "2") (pinfunction "2_2") (pintype "passive"))
      (node (ref "U1") (pin "7") (pinfunction "NRST_7") (pintype "bidirectional"))
    )
  )
)
